# frontplatine_v0_2.net
KiCad netlist of a schematic drawn in EAGLE
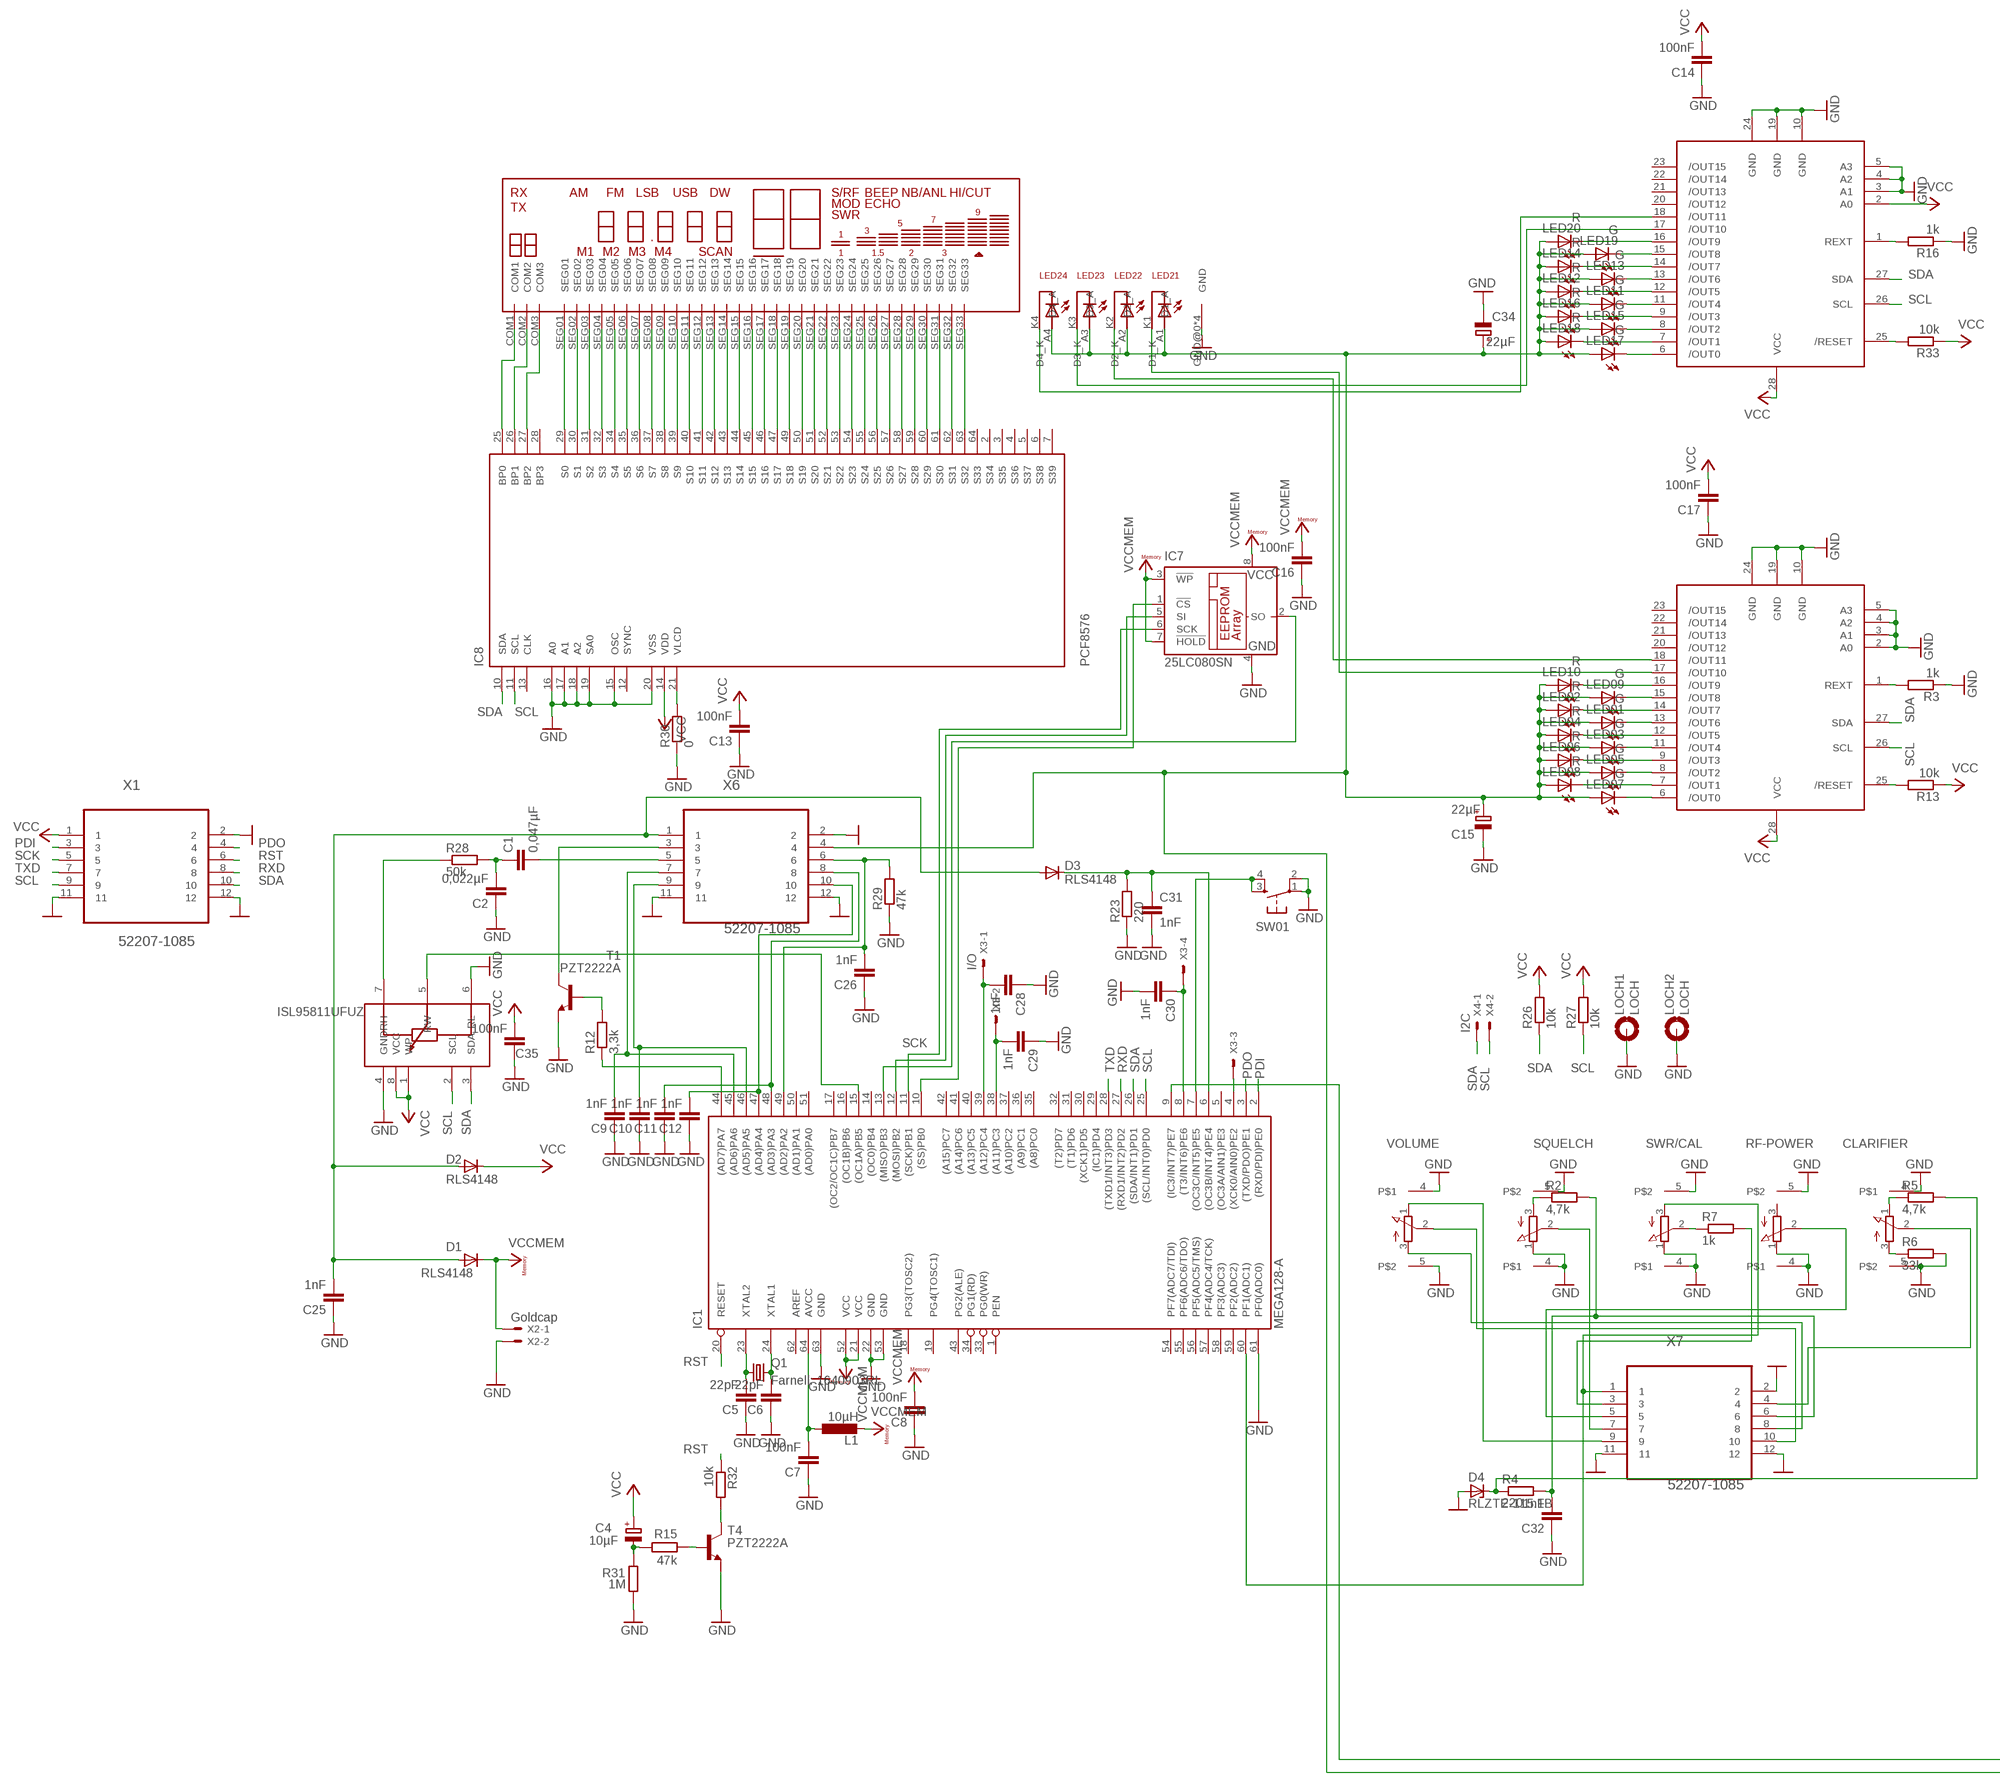
[diagram p0: schematic, sheet 1, part 1 of 2]
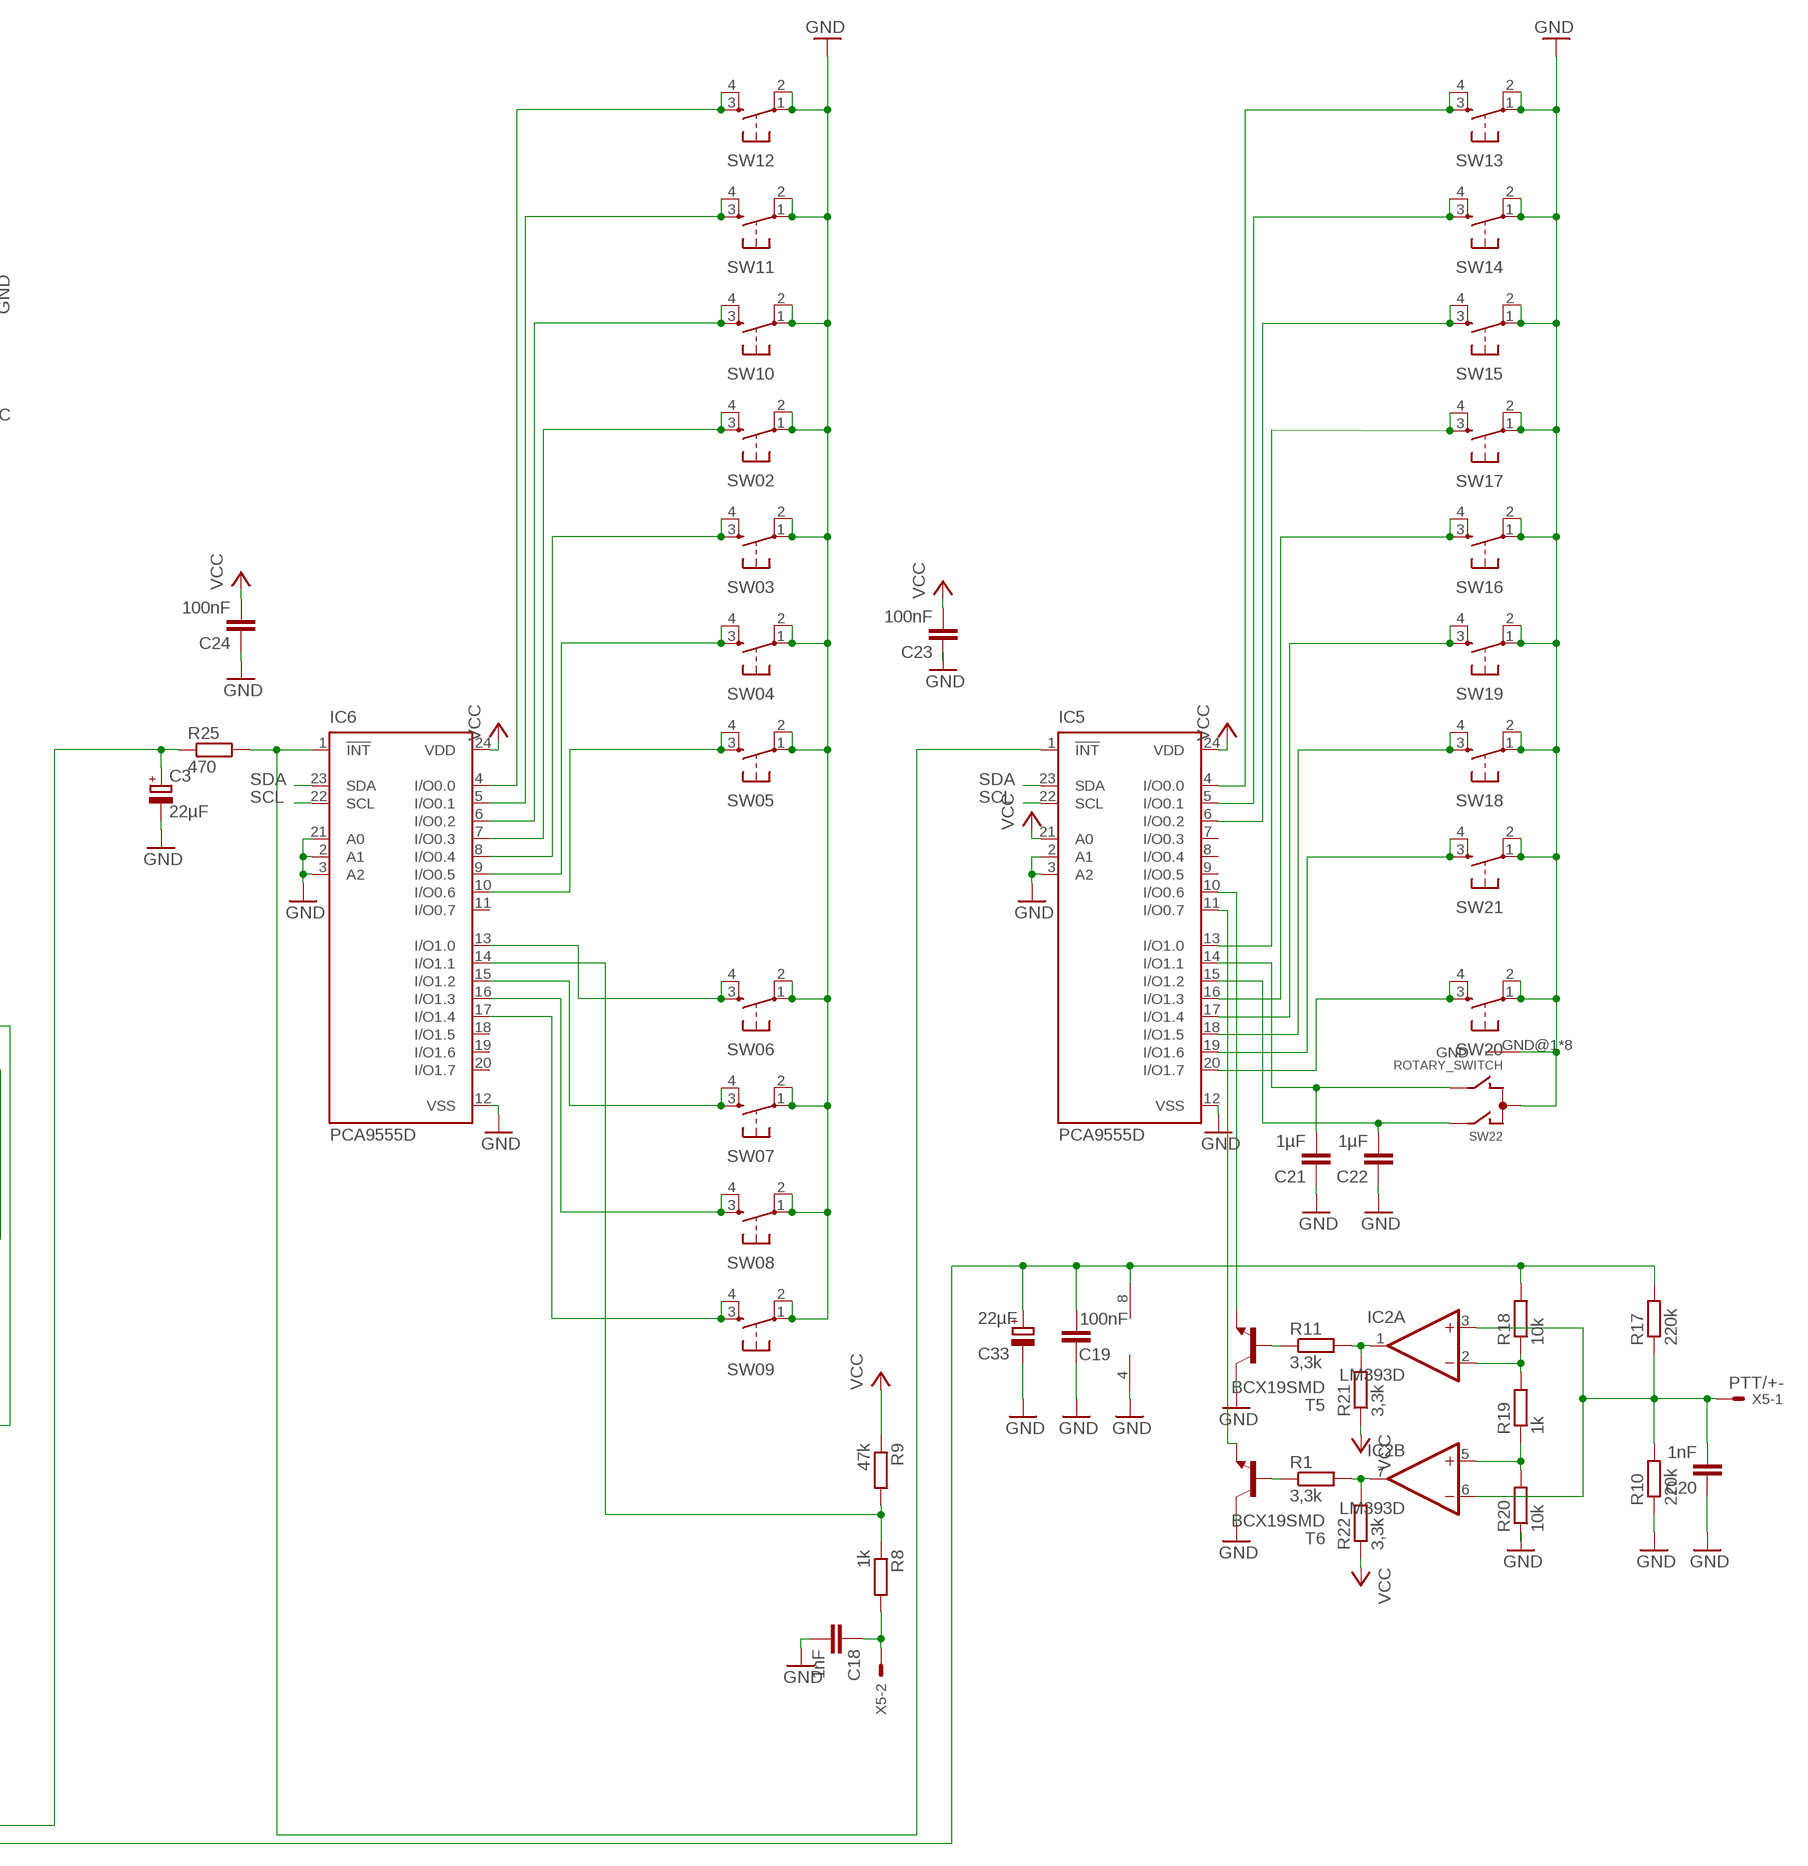
[diagram p1: schematic, sheet 1, part 2 of 2]

(export (version "E")
  (design (tool "Eeschema 10.0.6"))
  (components
    (comp (ref "C1")
      (value "0,047µF")
      (footprint "eagle-import:C1206")
      (libsource (lib "eagle-import") (part "C-EUC1206"))
    )
    (comp (ref "C2")
      (value "0,022µF")
      (footprint "eagle-import:C1206")
      (libsource (lib "eagle-import") (part "resistor_C-EUC1206"))
    )
    (comp (ref "C3")
      (value "22µF")
      (footprint "eagle-import:CT3216")
      (libsource (lib "eagle-import") (part "CPOL-EUCT3216"))
    )
    (comp (ref "C4")
      (value "10µF")
      (footprint "eagle-import:CT3216")
      (libsource (lib "eagle-import") (part "CPOL-EUCT3216"))
    )
    (comp (ref "C5")
      (value "22pF")
      (footprint "eagle-import:C1206")
      (libsource (lib "eagle-import") (part "resistor_C-EUC1206"))
    )
    (comp (ref "C6")
      (value "22pF")
      (footprint "eagle-import:C1206")
      (libsource (lib "eagle-import") (part "resistor_C-EUC1206"))
    )
    (comp (ref "C7")
      (value "100nF")
      (footprint "eagle-import:C1206")
      (libsource (lib "eagle-import") (part "resistor_C-EUC1206"))
    )
    (comp (ref "C8")
      (value "100nF")
      (footprint "eagle-import:C1206")
      (libsource (lib "eagle-import") (part "resistor_C-EUC1206"))
    )
    (comp (ref "C9")
      (value "1nF")
      (footprint "eagle-import:C1206")
      (libsource (lib "eagle-import") (part "resistor_C-EUC1206"))
    )
    (comp (ref "C10")
      (value "1nF")
      (footprint "eagle-import:C1206")
      (libsource (lib "eagle-import") (part "resistor_C-EUC1206"))
    )
    (comp (ref "C11")
      (value "1nF")
      (footprint "eagle-import:C1206")
      (libsource (lib "eagle-import") (part "resistor_C-EUC1206"))
    )
    (comp (ref "C12")
      (value "1nF")
      (footprint "eagle-import:C1206")
      (libsource (lib "eagle-import") (part "resistor_C-EUC1206"))
    )
    (comp (ref "C13")
      (value "100nF")
      (footprint "eagle-import:C1206")
      (libsource (lib "eagle-import") (part "resistor_C-EUC1206"))
    )
    (comp (ref "C14")
      (value "100nF")
      (footprint "eagle-import:C1206")
      (libsource (lib "eagle-import") (part "resistor_C-EUC1206"))
    )
    (comp (ref "C15")
      (value "22µF")
      (footprint "eagle-import:CT3216")
      (libsource (lib "eagle-import") (part "CPOL-EUCT3216"))
    )
    (comp (ref "C16")
      (value "100nF")
      (footprint "eagle-import:C1206")
      (libsource (lib "eagle-import") (part "resistor_C-EUC1206"))
    )
    (comp (ref "C17")
      (value "100nF")
      (footprint "eagle-import:C1206")
      (libsource (lib "eagle-import") (part "resistor_C-EUC1206"))
    )
    (comp (ref "C18")
      (value "1nF")
      (footprint "eagle-import:C1206")
      (libsource (lib "eagle-import") (part "resistor_C-EUC1206"))
    )
    (comp (ref "C19")
      (value "100nF")
      (footprint "eagle-import:C1206")
      (libsource (lib "eagle-import") (part "resistor_C-EUC1206"))
    )
    (comp (ref "C20")
      (value "1nF")
      (footprint "eagle-import:C1206")
      (libsource (lib "eagle-import") (part "resistor_C-EUC1206"))
    )
    (comp (ref "C21")
      (value "1µF")
      (footprint "eagle-import:C1206")
      (libsource (lib "eagle-import") (part "resistor_C-EUC1206"))
    )
    (comp (ref "C22")
      (value "1µF")
      (footprint "eagle-import:C1206")
      (libsource (lib "eagle-import") (part "resistor_C-EUC1206"))
    )
    (comp (ref "C23")
      (value "100nF")
      (footprint "eagle-import:C1206")
      (libsource (lib "eagle-import") (part "resistor_C-EUC1206"))
    )
    (comp (ref "C24")
      (value "100nF")
      (footprint "eagle-import:C1206")
      (libsource (lib "eagle-import") (part "resistor_C-EUC1206"))
    )
    (comp (ref "C25")
      (value "1nF")
      (footprint "eagle-import:C1206")
      (libsource (lib "eagle-import") (part "resistor_C-EUC1206"))
    )
    (comp (ref "C26")
      (value "1nF")
      (footprint "eagle-import:C1206")
      (libsource (lib "eagle-import") (part "resistor_C-EUC1206"))
    )
    (comp (ref "C28")
      (value "1nF")
      (footprint "eagle-import:C1206")
      (libsource (lib "eagle-import") (part "resistor_C-EUC1206"))
    )
    (comp (ref "C29")
      (value "1nF")
      (footprint "eagle-import:C1206")
      (libsource (lib "eagle-import") (part "resistor_C-EUC1206"))
    )
    (comp (ref "C30")
      (value "1nF")
      (footprint "eagle-import:C1206")
      (libsource (lib "eagle-import") (part "resistor_C-EUC1206"))
    )
    (comp (ref "C31")
      (value "1nF")
      (footprint "eagle-import:C1206")
      (libsource (lib "eagle-import") (part "resistor_C-EUC1206"))
    )
    (comp (ref "C32")
      (value "1nF")
      (footprint "eagle-import:C1206")
      (libsource (lib "eagle-import") (part "resistor_C-EUC1206"))
    )
    (comp (ref "C33")
      (value "22µF")
      (footprint "eagle-import:CT3216")
      (libsource (lib "eagle-import") (part "CPOL-EUCT3216"))
    )
    (comp (ref "C34")
      (value "22µF")
      (footprint "eagle-import:CT3216")
      (libsource (lib "eagle-import") (part "CPOL-EUCT3216"))
    )
    (comp (ref "C35")
      (value "100nF")
      (footprint "eagle-import:C1206")
      (libsource (lib "eagle-import") (part "resistor_C-EUC1206"))
    )
    (comp (ref "CLARIFIER")
      (value "POTI")
      (footprint "eagle-import:POTI")
      (libsource (lib "eagle-import") (part "POTI"))
    )
    (comp (ref "D1")
      (value "RLS4148")
      (footprint "eagle-import:SOD80C")
      (libsource (lib "eagle-import") (part "DIODE-SOD80C"))
    )
    (comp (ref "D2")
      (value "RLS4148")
      (footprint "eagle-import:SOD80C")
      (libsource (lib "eagle-import") (part "DIODE-SOD80C"))
    )
    (comp (ref "D3")
      (value "RLS4148")
      (footprint "eagle-import:SOD80C")
      (libsource (lib "eagle-import") (part "DIODE-SOD80C"))
    )
    (comp (ref "D4")
      (value "RLZTE-115.1B")
      (footprint "eagle-import:SOD80C")
      (libsource (lib "eagle-import") (part "ZENER-DIODESOD80C"))
    )
    (comp (ref "DISPLAY1")
      (value "DISPLAY")
      (footprint "eagle-import:DISPLAY")
      (libsource (lib "eagle-import") (part "DISPLAY"))
    )
    (comp (ref "IC1")
      (value "MEGA128-A")
      (footprint "eagle-import:TQFP64")
      (fields (field (name "MPN") "ATMEGA128-16AU"))
      (libsource (lib "eagle-import") (part "MEGA128-A"))
    )
    (comp (ref "IC2")
      (value "LM393D")
      (footprint "eagle-import:SO08")
      (libsource (lib "eagle-import") (part "LM393D"))
    )
    (comp (ref "IC3")
      (value "TLC59116")
      (footprint "eagle-import:TSSOP28")
      (libsource (lib "eagle-import") (part "TLC59116"))
    )
    (comp (ref "IC4")
      (value "TLC59116")
      (footprint "eagle-import:TSSOP28")
      (libsource (lib "eagle-import") (part "TLC59116"))
    )
    (comp (ref "IC5")
      (value "PCA9555D")
      (footprint "eagle-import:SO24")
      (fields (field (name "MPN") "PCA9555DW"))
      (libsource (lib "eagle-import") (part "PCA9555D"))
    )
    (comp (ref "IC6")
      (value "PCA9555D")
      (footprint "eagle-import:SO24")
      (fields (field (name "MPN") "PCA9555DW"))
      (libsource (lib "eagle-import") (part "PCA9555D"))
    )
    (comp (ref "IC7")
      (value "25LC080SN")
      (footprint "eagle-import:SO-08")
      (fields
        (field (name "MF") "MICROCHIP")
        (field (name "MPN") "25LC080/SN")
        (field (name "MPN_1") "25LC080/SN")
        (field (name "OC_FARNELL") "1137302")
        (field (name "OC_NEWARK") "96K4092")
      )
      (libsource (lib "eagle-import") (part "25SNLC080"))
    )
    (comp (ref "IC8")
      (value "PCF8576")
      (footprint "eagle-import:LQFP-ST-64-2")
      (libsource (lib "eagle-import") (part "PCF8576"))
    )
    (comp (ref "IC9")
      (value "ISL95811UFUZ")
      (footprint "eagle-import:MSOP8")
      (libsource (lib "eagle-import") (part "ISL95811UFUZ"))
    )
    (comp (ref "L1")
      (value "10µH")
      (footprint "eagle-import:L1812")
      (libsource (lib "eagle-import") (part "L-EUL1812"))
    )
    (comp (ref "LED01")
      (value "G")
      (footprint "eagle-import:CHIPLED_1206")
      (libsource (lib "eagle-import") (part "LEDCHIPLED_1206"))
    )
    (comp (ref "LED02")
      (value "R")
      (footprint "eagle-import:CHIPLED_1206")
      (libsource (lib "eagle-import") (part "LEDCHIPLED_1206"))
    )
    (comp (ref "LED03")
      (value "G")
      (footprint "eagle-import:CHIPLED_1206")
      (libsource (lib "eagle-import") (part "LEDCHIPLED_1206"))
    )
    (comp (ref "LED04")
      (value "R")
      (footprint "eagle-import:CHIPLED_1206")
      (libsource (lib "eagle-import") (part "LEDCHIPLED_1206"))
    )
    (comp (ref "LED05")
      (value "G")
      (footprint "eagle-import:CHIPLED_1206")
      (libsource (lib "eagle-import") (part "LEDCHIPLED_1206"))
    )
    (comp (ref "LED06")
      (value "R")
      (footprint "eagle-import:CHIPLED_1206")
      (libsource (lib "eagle-import") (part "LEDCHIPLED_1206"))
    )
    (comp (ref "LED07")
      (value "G")
      (footprint "eagle-import:CHIPLED_1206")
      (libsource (lib "eagle-import") (part "LEDCHIPLED_1206"))
    )
    (comp (ref "LED08")
      (value "R")
      (footprint "eagle-import:CHIPLED_1206")
      (libsource (lib "eagle-import") (part "LEDCHIPLED_1206"))
    )
    (comp (ref "LED09")
      (value "G")
      (footprint "eagle-import:CHIPLED_1206")
      (libsource (lib "eagle-import") (part "LEDCHIPLED_1206"))
    )
    (comp (ref "LED10")
      (value "R")
      (footprint "eagle-import:CHIPLED_1206")
      (libsource (lib "eagle-import") (part "LEDCHIPLED_1206"))
    )
    (comp (ref "LED11")
      (value "G")
      (footprint "eagle-import:CHIPLED_1206")
      (libsource (lib "eagle-import") (part "LEDCHIPLED_1206"))
    )
    (comp (ref "LED12")
      (value "R")
      (footprint "eagle-import:CHIPLED_1206")
      (libsource (lib "eagle-import") (part "LEDCHIPLED_1206"))
    )
    (comp (ref "LED13")
      (value "G")
      (footprint "eagle-import:CHIPLED_1206")
      (libsource (lib "eagle-import") (part "LEDCHIPLED_1206"))
    )
    (comp (ref "LED14")
      (value "R")
      (footprint "eagle-import:CHIPLED_1206")
      (libsource (lib "eagle-import") (part "LEDCHIPLED_1206"))
    )
    (comp (ref "LED15")
      (value "G")
      (footprint "eagle-import:CHIPLED_1206")
      (libsource (lib "eagle-import") (part "LEDCHIPLED_1206"))
    )
    (comp (ref "LED16")
      (value "R")
      (footprint "eagle-import:CHIPLED_1206")
      (libsource (lib "eagle-import") (part "LEDCHIPLED_1206"))
    )
    (comp (ref "LED17")
      (value "G")
      (footprint "eagle-import:CHIPLED_1206")
      (libsource (lib "eagle-import") (part "LEDCHIPLED_1206"))
    )
    (comp (ref "LED18")
      (value "R")
      (footprint "eagle-import:CHIPLED_1206")
      (libsource (lib "eagle-import") (part "LEDCHIPLED_1206"))
    )
    (comp (ref "LED19")
      (value "G")
      (footprint "eagle-import:CHIPLED_1206")
      (libsource (lib "eagle-import") (part "LEDCHIPLED_1206"))
    )
    (comp (ref "LED20")
      (value "R")
      (footprint "eagle-import:CHIPLED_1206")
      (libsource (lib "eagle-import") (part "LEDCHIPLED_1206"))
    )
    (comp (ref "LOCH1")
      (value "LOCH")
      (footprint "eagle-import:LOCH")
      (libsource (lib "eagle-import") (part "LOCH"))
    )
    (comp (ref "LOCH2")
      (value "LOCH")
      (footprint "eagle-import:LOCH")
      (libsource (lib "eagle-import") (part "LOCH"))
    )
    (comp (ref "Q1")
      (value "Farnell: 1640903RL")
      (footprint "eagle-import:HC49UP")
      (libsource (lib "eagle-import") (part "CRYSTALHC49UP"))
    )
    (comp (ref "R1")
      (value "3,3k")
      (footprint "eagle-import:R1206")
      (libsource (lib "eagle-import") (part "resistor_R-EU_R1206"))
    )
    (comp (ref "R2")
      (value "4,7k")
      (footprint "eagle-import:R1206")
      (libsource (lib "eagle-import") (part "resistor_R-EU_R1206"))
    )
    (comp (ref "R3")
      (value "1k")
      (footprint "eagle-import:R1206")
      (libsource (lib "eagle-import") (part "R-EU_R1206"))
    )
    (comp (ref "R4")
      (value "220")
      (footprint "eagle-import:R1206")
      (libsource (lib "eagle-import") (part "resistor_R-EU_R1206"))
    )
    (comp (ref "R5")
      (value "4,7k")
      (footprint "eagle-import:R1206")
      (libsource (lib "eagle-import") (part "resistor_R-EU_R1206"))
    )
    (comp (ref "R6")
      (value "33k")
      (footprint "eagle-import:R1206")
      (libsource (lib "eagle-import") (part "resistor_R-EU_R1206"))
    )
    (comp (ref "R7")
      (value "1k")
      (footprint "eagle-import:R1206")
      (libsource (lib "eagle-import") (part "resistor_R-EU_R1206"))
    )
    (comp (ref "R8")
      (value "1k")
      (footprint "eagle-import:R1206")
      (libsource (lib "eagle-import") (part "resistor_R-EU_R1206"))
    )
    (comp (ref "R9")
      (value "47k")
      (footprint "eagle-import:R1206")
      (libsource (lib "eagle-import") (part "resistor_R-EU_R1206"))
    )
    (comp (ref "R10")
      (value "220k")
      (footprint "eagle-import:R1206")
      (libsource (lib "eagle-import") (part "resistor_R-EU_R1206"))
    )
    (comp (ref "R11")
      (value "3,3k")
      (footprint "eagle-import:R1206")
      (libsource (lib "eagle-import") (part "resistor_R-EU_R1206"))
    )
    (comp (ref "R12")
      (value "3,3k")
      (footprint "eagle-import:R1206")
      (libsource (lib "eagle-import") (part "resistor_R-EU_R1206"))
    )
    (comp (ref "R13")
      (value "10k")
      (footprint "eagle-import:R1206")
      (libsource (lib "eagle-import") (part "resistor_R-EU_R1206"))
    )
    (comp (ref "R15")
      (value "47k")
      (footprint "eagle-import:R1206")
      (libsource (lib "eagle-import") (part "resistor_R-EU_R1206"))
    )
    (comp (ref "R16")
      (value "1k")
      (footprint "eagle-import:R1206")
      (libsource (lib "eagle-import") (part "R-EU_R1206"))
    )
    (comp (ref "R17")
      (value "220k")
      (footprint "eagle-import:R1206")
      (libsource (lib "eagle-import") (part "resistor_R-EU_R1206"))
    )
    (comp (ref "R18")
      (value "10k")
      (footprint "eagle-import:R1206")
      (libsource (lib "eagle-import") (part "resistor_R-EU_R1206"))
    )
    (comp (ref "R19")
      (value "1k")
      (footprint "eagle-import:R1206")
      (libsource (lib "eagle-import") (part "resistor_R-EU_R1206"))
    )
    (comp (ref "R20")
      (value "10k")
      (footprint "eagle-import:R1206")
      (libsource (lib "eagle-import") (part "resistor_R-EU_R1206"))
    )
    (comp (ref "R21")
      (value "3,3k")
      (footprint "eagle-import:R1206")
      (libsource (lib "eagle-import") (part "resistor_R-EU_R1206"))
    )
    (comp (ref "R22")
      (value "3,3k")
      (footprint "eagle-import:R1206")
      (libsource (lib "eagle-import") (part "resistor_R-EU_R1206"))
    )
    (comp (ref "R23")
      (value "220")
      (footprint "eagle-import:R1206")
      (libsource (lib "eagle-import") (part "resistor_R-EU_R1206"))
    )
    (comp (ref "R25")
      (value "470")
      (footprint "eagle-import:R1206")
      (libsource (lib "eagle-import") (part "resistor_R-EU_R1206"))
    )
    (comp (ref "R26")
      (value "10k")
      (footprint "eagle-import:R1206")
      (libsource (lib "eagle-import") (part "resistor_R-EU_R1206"))
    )
    (comp (ref "R27")
      (value "10k")
      (footprint "eagle-import:R1206")
      (libsource (lib "eagle-import") (part "resistor_R-EU_R1206"))
    )
    (comp (ref "R28")
      (value "50k")
      (footprint "eagle-import:R1206")
      (libsource (lib "eagle-import") (part "resistor_R-EU_R1206"))
    )
    (comp (ref "R29")
      (value "47k")
      (footprint "eagle-import:R1206")
      (libsource (lib "eagle-import") (part "resistor_R-EU_R1206"))
    )
    (comp (ref "R30")
      (value "0")
      (footprint "eagle-import:R1206")
      (libsource (lib "eagle-import") (part "resistor_R-EU_R1206"))
    )
    (comp (ref "R31")
      (value "1M")
      (footprint "eagle-import:R1206")
      (libsource (lib "eagle-import") (part "resistor_R-EU_R1206"))
    )
    (comp (ref "R32")
      (value "10k")
      (footprint "eagle-import:R1206")
      (libsource (lib "eagle-import") (part "resistor_R-EU_R1206"))
    )
    (comp (ref "R33")
      (value "10k")
      (footprint "eagle-import:R1206")
      (libsource (lib "eagle-import") (part "resistor_R-EU_R1206"))
    )
    (comp (ref "RF-POWER")
      (value "POTI")
      (footprint "eagle-import:POTI")
      (libsource (lib "eagle-import") (part "POTI"))
    )
    (comp (ref "SQUELCH")
      (value "POTI")
      (footprint "eagle-import:POTI")
      (libsource (lib "eagle-import") (part "POTI"))
    )
    (comp (ref "SW01")
      (value "TASTER")
      (footprint "eagle-import:TASTER")
      (libsource (lib "eagle-import") (part "TASTER"))
    )
    (comp (ref "SW02")
      (value "TASTER")
      (footprint "eagle-import:TASTER")
      (libsource (lib "eagle-import") (part "TASTER"))
    )
    (comp (ref "SW03")
      (value "TASTER")
      (footprint "eagle-import:TASTER")
      (libsource (lib "eagle-import") (part "TASTER"))
    )
    (comp (ref "SW04")
      (value "TASTER")
      (footprint "eagle-import:TASTER")
      (libsource (lib "eagle-import") (part "TASTER"))
    )
    (comp (ref "SW05")
      (value "TASTER")
      (footprint "eagle-import:TASTER")
      (libsource (lib "eagle-import") (part "TASTER"))
    )
    (comp (ref "SW06")
      (value "TASTER")
      (footprint "eagle-import:TASTER")
      (libsource (lib "eagle-import") (part "TASTER"))
    )
    (comp (ref "SW07")
      (value "TASTER")
      (footprint "eagle-import:TASTER")
      (libsource (lib "eagle-import") (part "TASTER"))
    )
    (comp (ref "SW08")
      (value "TASTER")
      (footprint "eagle-import:TASTER")
      (libsource (lib "eagle-import") (part "TASTER"))
    )
    (comp (ref "SW09")
      (value "TASTER")
      (footprint "eagle-import:TASTER")
      (libsource (lib "eagle-import") (part "TASTER"))
    )
    (comp (ref "SW10")
      (value "TASTER")
      (footprint "eagle-import:TASTER")
      (libsource (lib "eagle-import") (part "TASTER"))
    )
    (comp (ref "SW11")
      (value "TASTER")
      (footprint "eagle-import:TASTER")
      (libsource (lib "eagle-import") (part "TASTER"))
    )
    (comp (ref "SW12")
      (value "TASTER")
      (footprint "eagle-import:TASTER")
      (libsource (lib "eagle-import") (part "TASTER"))
    )
    (comp (ref "SW13")
      (value "TASTER")
      (footprint "eagle-import:TASTER")
      (libsource (lib "eagle-import") (part "TASTER"))
    )
    (comp (ref "SW14")
      (value "TASTER")
      (footprint "eagle-import:TASTER")
      (libsource (lib "eagle-import") (part "TASTER"))
    )
    (comp (ref "SW15")
      (value "TASTER")
      (footprint "eagle-import:TASTER")
      (libsource (lib "eagle-import") (part "TASTER"))
    )
    (comp (ref "SW16")
      (value "TASTER")
      (footprint "eagle-import:TASTER")
      (libsource (lib "eagle-import") (part "TASTER"))
    )
    (comp (ref "SW17")
      (value "TASTER")
      (footprint "eagle-import:TASTER")
      (libsource (lib "eagle-import") (part "TASTER"))
    )
    (comp (ref "SW18")
      (value "TASTER")
      (footprint "eagle-import:TASTER")
      (libsource (lib "eagle-import") (part "TASTER"))
    )
    (comp (ref "SW19")
      (value "TASTER")
      (footprint "eagle-import:TASTER")
      (libsource (lib "eagle-import") (part "TASTER"))
    )
    (comp (ref "SW20")
      (value "TASTER")
      (footprint "eagle-import:TASTER")
      (libsource (lib "eagle-import") (part "TASTER"))
    )
    (comp (ref "SW21")
      (value "TASTER")
      (footprint "eagle-import:TASTER")
      (libsource (lib "eagle-import") (part "TASTER"))
    )
    (comp (ref "SW22")
      (value "ROTARY_SWITCH")
      (footprint "eagle-import:ROTARY_SWITCH")
      (libsource (lib "eagle-import") (part "ROTARY_SWITCH"))
    )
    (comp (ref "SWR/CAL")
      (value "POTI")
      (footprint "eagle-import:POTI")
      (libsource (lib "eagle-import") (part "POTI"))
    )
    (comp (ref "T1")
      (value "PZT2222A")
      (footprint "eagle-import:SOT223")
      (libsource (lib "eagle-import") (part "-NPN-SOT223PZT2222A"))
    )
    (comp (ref "T4")
      (value "PZT2222A")
      (footprint "eagle-import:SOT223")
      (libsource (lib "eagle-import") (part "-NPN-SOT223PZT2222A"))
    )
    (comp (ref "T5")
      (value "BCX19SMD")
      (footprint "eagle-import:SOT23-BEC")
      (libsource (lib "eagle-import") (part "BCX19SMD"))
    )
    (comp (ref "T6")
      (value "BCX19SMD")
      (footprint "eagle-import:SOT23-BEC")
      (libsource (lib "eagle-import") (part "BCX19SMD"))
    )
    (comp (ref "VOLUME")
      (value "POTI")
      (footprint "eagle-import:POTI")
      (libsource (lib "eagle-import") (part "POTI"))
    )
    (comp (ref "X1")
      (value "52207-1085")
      (footprint "eagle-import:MOLEX_52207-1085")
      (libsource (lib "eagle-import") (part "52207-1085"))
    )
    (comp (ref "X2")
      (value "Goldcap")
      (footprint "eagle-import:53047-02")
      (fields (field (name "MF") "MOLEX") (field (name "MPN") "53047-0210"))
      (libsource (lib "eagle-import") (part "53?-02047"))
    )
    (comp (ref "X3")
      (value "I/O")
      (footprint "eagle-import:53047-04")
      (fields (field (name "MF") "WALDOM/MOLEX") (field (name "MPN") "53047-0410"))
      (libsource (lib "eagle-import") (part "53?-04047"))
    )
    (comp (ref "X4")
      (value "I2C")
      (footprint "eagle-import:53047-02")
      (fields
        (field (name "MF") "MOLEX")
        (field (name "MPN") "53047-0210")
        (field (name "MF_1") "MOLEX")
        (field (name "MPN_1") "53047-0210")
        (field (name "OC_FARNELL") "9733051")
        (field (name "OC_NEWARK") "57H4701")
      )
      (libsource (lib "eagle-import") (part "53?-02047"))
    )
    (comp (ref "X5")
      (value "PTT/+-")
      (footprint "eagle-import:53047-02")
      (fields
        (field (name "MF") "MOLEX")
        (field (name "MPN") "53047-0210")
        (field (name "MF_1") "MOLEX")
        (field (name "MPN_1") "53047-0210")
        (field (name "OC_FARNELL") "9733051")
        (field (name "OC_NEWARK") "57H4701")
      )
      (libsource (lib "eagle-import") (part "53?-02047"))
    )
    (comp (ref "X6")
      (value "52207-1085")
      (footprint "eagle-import:MOLEX_52207-1085")
      (fields
        (field (name "MPN") "52207-1085")
        (field (name "OC_FARNELL") "1079938")
        (field (name "OC_NEWARK") "58J9503")
        (field (name "PACKAGE") "SOCKET FPC, SMT, 1MM, 10 WAY")
      )
      (libsource (lib "eagle-import") (part "52207-1085"))
    )
    (comp (ref "X7")
      (value "52207-1085")
      (footprint "eagle-import:MOLEX_52207-1085")
      (fields
        (field (name "MPN") "52207-1085")
        (field (name "OC_FARNELL") "1079938")
        (field (name "OC_NEWARK") "58J9503")
        (field (name "PACKAGE") "SOCKET FPC, SMT, 1MM, 10 WAY")
      )
      (libsource (lib "eagle-import") (part "52207-1085"))
    )
  )
  (nets
    (net (code "1") (name "/PDI") (class "Default")
      (node (ref "IC1") (pin "2") (pinfunction "(RXD/PDI)PE0_2") (pintype "bidirectional"))
      (node (ref "X1") (pin "3") (pinfunction "3_3") (pintype "passive"))
    )
    (net (code "2") (name "/PDO") (class "Default")
      (node (ref "IC1") (pin "3") (pinfunction "(TXD/PDO)PE1_3") (pintype "bidirectional"))
      (node (ref "X1") (pin "4") (pinfunction "4_4") (pintype "passive"))
    )
    (net (code "3") (name "/RST") (class "Default")
      (node (ref "IC1") (pin "20") (pinfunction "RESET_20") (pintype "input"))
      (node (ref "R32") (pin "1") (pinfunction "1_1") (pintype "passive"))
      (node (ref "X1") (pin "6") (pinfunction "6_6") (pintype "passive"))
    )
    (net (code "4") (name "/RXD") (class "Default")
      (node (ref "IC1") (pin "27") (pinfunction "(RXD1/INT2)PD2_27") (pintype "bidirectional"))
      (node (ref "X1") (pin "8") (pinfunction "8_8") (pintype "passive"))
    )
    (net (code "5") (name "/SCK") (class "Default")
      (node (ref "IC1") (pin "11") (pinfunction "(SCK)PB1_11") (pintype "bidirectional"))
      (node (ref "IC7") (pin "6") (pinfunction "SCK_6") (pintype "input"))
      (node (ref "X1") (pin "5") (pinfunction "5_5") (pintype "passive"))
    )
    (net (code "6") (name "/SCL") (class "Default")
      (node (ref "IC1") (pin "25") (pinfunction "(SCL/INT0)PD0_25") (pintype "bidirectional"))
      (node (ref "IC3") (pin "26") (pinfunction "SCL_26") (pintype "bidirectional"))
      (node (ref "IC4") (pin "26") (pinfunction "SCL_26") (pintype "bidirectional"))
      (node (ref "IC5") (pin "22") (pinfunction "SCL_22") (pintype "input"))
      (node (ref "IC6") (pin "22") (pinfunction "SCL_22") (pintype "input"))
      (node (ref "IC8") (pin "11") (pinfunction "SCL_11") (pintype "input"))
      (node (ref "IC9") (pin "2") (pinfunction "SCL_2") (pintype "bidirectional"))
      (node (ref "R27") (pin "1") (pinfunction "1_1") (pintype "passive"))
      (node (ref "X1") (pin "9") (pinfunction "9_9") (pintype "passive"))
      (node (ref "X4") (pin "2") (pinfunction "S_2") (pintype "passive"))
    )
    (net (code "7") (name "/SDA") (class "Default")
      (node (ref "IC1") (pin "26") (pinfunction "(SDA/INT1)PD1_26") (pintype "bidirectional"))
      (node (ref "IC3") (pin "27") (pinfunction "SDA_27") (pintype "bidirectional"))
      (node (ref "IC4") (pin "27") (pinfunction "SDA_27") (pintype "bidirectional"))
      (node (ref "IC5") (pin "23") (pinfunction "SDA_23") (pintype "bidirectional"))
      (node (ref "IC6") (pin "23") (pinfunction "SDA_23") (pintype "bidirectional"))
      (node (ref "IC8") (pin "10") (pinfunction "SDA_10") (pintype "bidirectional"))
      (node (ref "IC9") (pin "3") (pinfunction "SDA_3") (pintype "input"))
      (node (ref "R26") (pin "1") (pinfunction "1_1") (pintype "passive"))
      (node (ref "X1") (pin "10") (pinfunction "10_10") (pintype "passive"))
      (node (ref "X4") (pin "1") (pinfunction "S_1") (pintype "passive"))
    )
    (net (code "8") (name "/TXD") (class "Default")
      (node (ref "IC1") (pin "28") (pinfunction "(TXD1/INT3)PD3_28") (pintype "bidirectional"))
      (node (ref "X1") (pin "7") (pinfunction "7_7") (pintype "passive"))
    )
    (net (code "9") (name "GND") (class "Default")
      (node (ref "C10") (pin "1") (pinfunction "1_1") (pintype "passive"))
      (node (ref "C11") (pin "1") (pinfunction "1_1") (pintype "passive"))
      (node (ref "C12") (pin "1") (pinfunction "1_1") (pintype "passive"))
      (node (ref "C13") (pin "1") (pinfunction "1_1") (pintype "passive"))
      (node (ref "C14") (pin "1") (pinfunction "1_1") (pintype "passive"))
      (node (ref "C15") (pin "-") (pinfunction "-_-") (pintype "passive"))
      (node (ref "C16") (pin "1") (pinfunction "1_1") (pintype "passive"))
      (node (ref "C17") (pin "1") (pinfunction "1_1") (pintype "passive"))
      (node (ref "C18") (pin "2") (pinfunction "2_2") (pintype "passive"))
      (node (ref "C19") (pin "1") (pinfunction "1_1") (pintype "passive"))
      (node (ref "C2") (pin "1") (pinfunction "1_1") (pintype "passive"))
      (node (ref "C20") (pin "1") (pinfunction "1_1") (pintype "passive"))
      (node (ref "C21") (pin "1") (pinfunction "1_1") (pintype "passive"))
      (node (ref "C22") (pin "1") (pinfunction "1_1") (pintype "passive"))
      (node (ref "C23") (pin "1") (pinfunction "1_1") (pintype "passive"))
      (node (ref "C24") (pin "1") (pinfunction "1_1") (pintype "passive"))
      (node (ref "C25") (pin "1") (pinfunction "1_1") (pintype "passive"))
      (node (ref "C26") (pin "1") (pinfunction "1_1") (pintype "passive"))
      (node (ref "C28") (pin "1") (pinfunction "1_1") (pintype "passive"))
      (node (ref "C29") (pin "1") (pinfunction "1_1") (pintype "passive"))
      (node (ref "C3") (pin "-") (pinfunction "-_-") (pintype "passive"))
      (node (ref "C30") (pin "2") (pinfunction "2_2") (pintype "passive"))
      (node (ref "C31") (pin "2") (pinfunction "2_2") (pintype "passive"))
      (node (ref "C32") (pin "1") (pinfunction "1_1") (pintype "passive"))
      (node (ref "C33") (pin "-") (pinfunction "-_-") (pintype "passive"))
      (node (ref "C34") (pin "-") (pinfunction "-_-") (pintype "passive"))
      (node (ref "C35") (pin "1") (pinfunction "1_1") (pintype "passive"))
      (node (ref "C5") (pin "1") (pinfunction "1_1") (pintype "passive"))
      (node (ref "C6") (pin "1") (pinfunction "1_1") (pintype "passive"))
      (node (ref "C7") (pin "1") (pinfunction "1_1") (pintype "passive"))
      (node (ref "C8") (pin "1") (pinfunction "1_1") (pintype "passive"))
      (node (ref "C9") (pin "1") (pinfunction "1_1") (pintype "passive"))
      (node (ref "CLARIFIER") (pin "4") (pinfunction "P$1_4") (pintype "power_in"))
      (node (ref "CLARIFIER") (pin "5") (pinfunction "P$2_5") (pintype "power_in"))
      (node (ref "D4") (pin "A") (pinfunction "A_A") (pintype "passive"))
      (node (ref "DISPLAY1") (pin "GND@0") (pinfunction "GND_GND@0") (pintype "power_in"))
      (node (ref "DISPLAY1") (pin "GND@3") (pinfunction "GND_GND@3") (pintype "power_in"))
      (node (ref "DISPLAY1") (pin "GND@6") (pinfunction "GND_GND@6") (pintype "power_in"))
      (node (ref "DISPLAY1") (pin "GND@7") (pinfunction "GND_GND@7") (pintype "power_in"))
      (node (ref "IC1") (pin "22") (pinfunction "GND_22") (pintype "power_in"))
      (node (ref "IC1") (pin "53") (pinfunction "GND_53") (pintype "power_in"))
      (node (ref "IC1") (pin "61") (pinfunction "PF0(ADC0)_61") (pintype "input"))
      (node (ref "IC1") (pin "63") (pinfunction "GND_63") (pintype "power_in"))
      (node (ref "IC2") (pin "4") (pinfunction "V-_4") (pintype "power_in"))
      (node (ref "IC3") (pin "10") (pinfunction "GND_10") (pintype "bidirectional"))
      (node (ref "IC3") (pin "19") (pinfunction "GND_19") (pintype "bidirectional"))
      (node (ref "IC3") (pin "2") (pinfunction "A0_2") (pintype "bidirectional"))
      (node (ref "IC3") (pin "24") (pinfunction "GND_24") (pintype "bidirectional"))
      (node (ref "IC3") (pin "3") (pinfunction "A1_3") (pintype "bidirectional"))
      (node (ref "IC3") (pin "4") (pinfunction "A2_4") (pintype "bidirectional"))
      (node (ref "IC3") (pin "5") (pinfunction "A3_5") (pintype "bidirectional"))
      (node (ref "IC4") (pin "10") (pinfunction "GND_10") (pintype "bidirectional"))
      (node (ref "IC4") (pin "19") (pinfunction "GND_19") (pintype "bidirectional"))
      (node (ref "IC4") (pin "24") (pinfunction "GND_24") (pintype "bidirectional"))
      (node (ref "IC4") (pin "3") (pinfunction "A1_3") (pintype "bidirectional"))
      (node (ref "IC4") (pin "4") (pinfunction "A2_4") (pintype "bidirectional"))
      (node (ref "IC4") (pin "5") (pinfunction "A3_5") (pintype "bidirectional"))
      (node (ref "IC5") (pin "12") (pinfunction "VSS_12") (pintype "power_in"))
      (node (ref "IC5") (pin "2") (pinfunction "A1_2") (pintype "input"))
      (node (ref "IC5") (pin "3") (pinfunction "A2_3") (pintype "input"))
      (node (ref "IC6") (pin "12") (pinfunction "VSS_12") (pintype "power_in"))
      (node (ref "IC6") (pin "2") (pinfunction "A1_2") (pintype "input"))
      (node (ref "IC6") (pin "21") (pinfunction "A0_21") (pintype "input"))
      (node (ref "IC6") (pin "3") (pinfunction "A2_3") (pintype "input"))
      (node (ref "IC7") (pin "4") (pinfunction "GND_4") (pintype "power_in"))
      (node (ref "IC8") (pin "15") (pinfunction "OSC_15") (pintype "input"))
      (node (ref "IC8") (pin "16") (pinfunction "A0_16") (pintype "input"))
      (node (ref "IC8") (pin "17") (pinfunction "A1_17") (pintype "input"))
      (node (ref "IC8") (pin "18") (pinfunction "A2_18") (pintype "input"))
      (node (ref "IC8") (pin "19") (pinfunction "SA0_19") (pintype "input"))
      (node (ref "IC8") (pin "20") (pinfunction "VSS_20") (pintype "power_in"))
      (node (ref "IC9") (pin "4") (pinfunction "GND_4") (pintype "power_in"))
      (node (ref "IC9") (pin "6") (pinfunction "RL_6") (pintype "bidirectional"))
      (node (ref "LOCH1") (pin "B3,0") (pinfunction "MOUNT_B3,0") (pintype "passive"))
      (node (ref "LOCH2") (pin "B3,0") (pinfunction "MOUNT_B3,0") (pintype "passive"))
      (node (ref "R10") (pin "1") (pinfunction "1_1") (pintype "passive"))
      (node (ref "R16") (pin "1") (pinfunction "1_1") (pintype "passive"))
      (node (ref "R20") (pin "1") (pinfunction "1_1") (pintype "passive"))
      (node (ref "R23") (pin "1") (pinfunction "1_1") (pintype "passive"))
      (node (ref "R29") (pin "1") (pinfunction "1_1") (pintype "passive"))
      (node (ref "R3") (pin "1") (pinfunction "1_1") (pintype "passive"))
      (node (ref "R30") (pin "1") (pinfunction "1_1") (pintype "passive"))
      (node (ref "R31") (pin "2") (pinfunction "2_2") (pintype "passive"))
      (node (ref "R6") (pin "2") (pinfunction "2_2") (pintype "passive"))
      (node (ref "RF-POWER") (pin "1") (pinfunction "E_1") (pintype "passive"))
      (node (ref "RF-POWER") (pin "4") (pinfunction "P$1_4") (pintype "power_in"))
      (node (ref "RF-POWER") (pin "5") (pinfunction "P$2_5") (pintype "power_in"))
      (node (ref "SQUELCH") (pin "1") (pinfunction "E_1") (pintype "passive"))
      (node (ref "SQUELCH") (pin "4") (pinfunction "P$1_4") (pintype "power_in"))
      (node (ref "SQUELCH") (pin "5") (pinfunction "P$2_5") (pintype "power_in"))
      (node (ref "SW01") (pin "1") (pinfunction "1_1") (pintype "passive"))
      (node (ref "SW01") (pin "2") (pinfunction "2_2") (pintype "passive"))
      (node (ref "SW02") (pin "1") (pinfunction "1_1") (pintype "passive"))
      (node (ref "SW02") (pin "2") (pinfunction "2_2") (pintype "passive"))
      (node (ref "SW03") (pin "1") (pinfunction "1_1") (pintype "passive"))
      (node (ref "SW03") (pin "2") (pinfunction "2_2") (pintype "passive"))
      (node (ref "SW04") (pin "1") (pinfunction "1_1") (pintype "passive"))
      (node (ref "SW04") (pin "2") (pinfunction "2_2") (pintype "passive"))
      (node (ref "SW05") (pin "1") (pinfunction "1_1") (pintype "passive"))
      (node (ref "SW05") (pin "2") (pinfunction "2_2") (pintype "passive"))
      (node (ref "SW06") (pin "1") (pinfunction "1_1") (pintype "passive"))
      (node (ref "SW06") (pin "2") (pinfunction "2_2") (pintype "passive"))
      (node (ref "SW07") (pin "1") (pinfunction "1_1") (pintype "passive"))
      (node (ref "SW07") (pin "2") (pinfunction "2_2") (pintype "passive"))
      (node (ref "SW08") (pin "1") (pinfunction "1_1") (pintype "passive"))
      (node (ref "SW08") (pin "2") (pinfunction "2_2") (pintype "passive"))
      (node (ref "SW09") (pin "1") (pinfunction "1_1") (pintype "passive"))
      (node (ref "SW09") (pin "2") (pinfunction "2_2") (pintype "passive"))
      (node (ref "SW10") (pin "1") (pinfunction "1_1") (pintype "passive"))
      (node (ref "SW10") (pin "2") (pinfunction "2_2") (pintype "passive"))
      (node (ref "SW11") (pin "1") (pinfunction "1_1") (pintype "passive"))
      (node (ref "SW11") (pin "2") (pinfunction "2_2") (pintype "passive"))
      (node (ref "SW12") (pin "1") (pinfunction "1_1") (pintype "passive"))
      (node (ref "SW12") (pin "2") (pinfunction "2_2") (pintype "passive"))
      (node (ref "SW13") (pin "1") (pinfunction "1_1") (pintype "passive"))
      (node (ref "SW13") (pin "2") (pinfunction "2_2") (pintype "passive"))
      (node (ref "SW14") (pin "1") (pinfunction "1_1") (pintype "passive"))
      (node (ref "SW14") (pin "2") (pinfunction "2_2") (pintype "passive"))
      (node (ref "SW15") (pin "1") (pinfunction "1_1") (pintype "passive"))
      (node (ref "SW15") (pin "2") (pinfunction "2_2") (pintype "passive"))
      (node (ref "SW16") (pin "1") (pinfunction "1_1") (pintype "passive"))
      (node (ref "SW16") (pin "2") (pinfunction "2_2") (pintype "passive"))
      (node (ref "SW17") (pin "1") (pinfunction "1_1") (pintype "passive"))
      (node (ref "SW17") (pin "2") (pinfunction "2_2") (pintype "passive"))
      (node (ref "SW18") (pin "1") (pinfunction "1_1") (pintype "passive"))
      (node (ref "SW18") (pin "2") (pinfunction "2_2") (pintype "passive"))
      (node (ref "SW19") (pin "1") (pinfunction "1_1") (pintype "passive"))
      (node (ref "SW19") (pin "2") (pinfunction "2_2") (pintype "passive"))
      (node (ref "SW20") (pin "1") (pinfunction "1_1") (pintype "passive"))
      (node (ref "SW20") (pin "2") (pinfunction "2_2") (pintype "passive"))
      (node (ref "SW21") (pin "1") (pinfunction "1_1") (pintype "passive"))
      (node (ref "SW21") (pin "2") (pinfunction "2_2") (pintype "passive"))
      (node (ref "SW22") (pin "C") (pinfunction "C_C") (pintype "passive"))
      (node (ref "SW22") (pin "GND@1") (pinfunction "GND_GND@1") (pintype "power_in"))
      (node (ref "SW22") (pin "GND@2") (pinfunction "GND_GND@2") (pintype "power_in"))
      (node (ref "SW22") (pin "GND@3") (pinfunction "GND_GND@3") (pintype "power_in"))
      (node (ref "SW22") (pin "GND@4") (pinfunction "GND_GND@4") (pintype "power_in"))
      (node (ref "SW22") (pin "GND@5") (pinfunction "GND_GND@5") (pintype "power_in"))
      (node (ref "SW22") (pin "GND@6") (pinfunction "GND_GND@6") (pintype "power_in"))
      (node (ref "SW22") (pin "GND@7") (pinfunction "GND_GND@7") (pintype "power_in"))
      (node (ref "SW22") (pin "GND@8") (pinfunction "GND_GND@8") (pintype "power_in"))
      (node (ref "SWR/CAL") (pin "1") (pinfunction "E_1") (pintype "passive"))
      (node (ref "SWR/CAL") (pin "4") (pinfunction "P$1_4") (pintype "power_in"))
      (node (ref "SWR/CAL") (pin "5") (pinfunction "P$2_5") (pintype "power_in"))
      (node (ref "T1") (pin "3") (pinfunction "E_3") (pintype "passive"))
      (node (ref "T4") (pin "3") (pinfunction "E_3") (pintype "passive"))
      (node (ref "T5") (pin "C") (pinfunction "C_C") (pintype "passive"))
      (node (ref "T6") (pin "C") (pinfunction "C_C") (pintype "passive"))
      (node (ref "VOLUME") (pin "4") (pinfunction "P$1_4") (pintype "power_in"))
      (node (ref "VOLUME") (pin "5") (pinfunction "P$2_5") (pintype "power_in"))
      (node (ref "X1") (pin "11") (pinfunction "11_11") (pintype "passive"))
      (node (ref "X1") (pin "12") (pinfunction "12_12") (pintype "passive"))
      (node (ref "X1") (pin "2") (pinfunction "2_2") (pintype "passive"))
      (node (ref "X2") (pin "2") (pinfunction "S_2") (pintype "passive"))
      (node (ref "X6") (pin "11") (pinfunction "11_11") (pintype "passive"))
      (node (ref "X6") (pin "12") (pinfunction "12_12") (pintype "passive"))
      (node (ref "X6") (pin "2") (pinfunction "2_2") (pintype "passive"))
      (node (ref "X7") (pin "11") (pinfunction "11_11") (pintype "passive"))
      (node (ref "X7") (pin "12") (pinfunction "12_12") (pintype "passive"))
      (node (ref "X7") (pin "2") (pinfunction "2_2") (pintype "passive"))
    )
    (net (code "10") (name "Net-(C1-Pad1)") (class "Default")
      (node (ref "C1") (pin "1") (pinfunction "1_1") (pintype "passive"))
      (node (ref "C2") (pin "2") (pinfunction "2_2") (pintype "passive"))
      (node (ref "R28") (pin "2") (pinfunction "2_2") (pintype "passive"))
    )
    (net (code "11") (name "Net-(C1-Pad2)") (class "Default")
      (node (ref "C1") (pin "2") (pinfunction "2_2") (pintype "passive"))
      (node (ref "X6") (pin "5") (pinfunction "5_5") (pintype "passive"))
    )
    (net (code "12") (name "Net-(C4-Pad-)") (class "Default")
      (node (ref "C4") (pin "-") (pinfunction "-_-") (pintype "passive"))
      (node (ref "R15") (pin "2") (pinfunction "2_2") (pintype "passive"))
      (node (ref "R31") (pin "1") (pinfunction "1_1") (pintype "passive"))
    )
    (net (code "13") (name "Net-(C25-Pad2)") (class "Default")
      (node (ref "C25") (pin "2") (pinfunction "2_2") (pintype "passive"))
      (node (ref "D1") (pin "A") (pinfunction "A_A") (pintype "passive"))
      (node (ref "D2") (pin "A") (pinfunction "A_A") (pintype "passive"))
      (node (ref "D3") (pin "A") (pinfunction "A_A") (pintype "passive"))
      (node (ref "X6") (pin "1") (pinfunction "1_1") (pintype "passive"))
    )
    (net (code "14") (name "Net-(C32-Pad2)") (class "Default")
      (node (ref "C32") (pin "2") (pinfunction "2_2") (pintype "passive"))
      (node (ref "R2") (pin "2") (pinfunction "2_2") (pintype "passive"))
      (node (ref "R4") (pin "2") (pinfunction "2_2") (pintype "passive"))
      (node (ref "X7") (pin "6") (pinfunction "6_6") (pintype "passive"))
    )
    (net (code "15") (name "Net-(CLARIFIER-A)") (class "Default")
      (node (ref "CLARIFIER") (pin "3") (pinfunction "A_3") (pintype "passive"))
      (node (ref "R6") (pin "1") (pinfunction "1_1") (pintype "passive"))
    )
    (net (code "16") (name "Net-(CLARIFIER-E)") (class "Default")
      (node (ref "CLARIFIER") (pin "1") (pinfunction "E_1") (pintype "passive"))
      (node (ref "R5") (pin "1") (pinfunction "1_1") (pintype "passive"))
    )
    (net (code "17") (name "Net-(CLARIFIER-S)") (class "Default")
      (node (ref "CLARIFIER") (pin "2") (pinfunction "S_2") (pintype "passive"))
      (node (ref "X7") (pin "4") (pinfunction "4_4") (pintype "passive"))
    )
    (net (code "18") (name "Net-(D4-PadC)") (class "Default")
      (node (ref "D4") (pin "C") (pinfunction "C_C") (pintype "passive"))
      (node (ref "R4") (pin "1") (pinfunction "1_1") (pintype "passive"))
      (node (ref "R5") (pin "2") (pinfunction "2_2") (pintype "passive"))
    )
    (net (code "19") (name "Net-(DISPLAY1-D1_A)") (class "Default")
      (node (ref "C15") (pin "+") (pinfunction "+_+") (pintype "passive"))
      (node (ref "C19") (pin "2") (pinfunction "2_2") (pintype "passive"))
      (node (ref "C33") (pin "+") (pinfunction "+_+") (pintype "passive"))
      (node (ref "C34") (pin "+") (pinfunction "+_+") (pintype "passive"))
      (node (ref "DISPLAY1") (pin "A1") (pinfunction "D1_A_A1") (pintype "input"))
      (node (ref "DISPLAY1") (pin "A2") (pinfunction "D2_A_A2") (pintype "input"))
      (node (ref "DISPLAY1") (pin "A3") (pinfunction "D3_A_A3") (pintype "input"))
      (node (ref "DISPLAY1") (pin "A4") (pinfunction "D4_A_A4") (pintype "input"))
      (node (ref "IC2") (pin "8") (pinfunction "V+_8") (pintype "power_in"))
      (node (ref "LED01") (pin "A") (pinfunction "A_A") (pintype "passive"))
      (node (ref "LED02") (pin "A") (pinfunction "A_A") (pintype "passive"))
      (node (ref "LED03") (pin "A") (pinfunction "A_A") (pintype "passive"))
      (node (ref "LED04") (pin "A") (pinfunction "A_A") (pintype "passive"))
      (node (ref "LED05") (pin "A") (pinfunction "A_A") (pintype "passive"))
      (node (ref "LED06") (pin "A") (pinfunction "A_A") (pintype "passive"))
      (node (ref "LED07") (pin "A") (pinfunction "A_A") (pintype "passive"))
      (node (ref "LED08") (pin "A") (pinfunction "A_A") (pintype "passive"))
      (node (ref "LED09") (pin "A") (pinfunction "A_A") (pintype "passive"))
      (node (ref "LED10") (pin "A") (pinfunction "A_A") (pintype "passive"))
      (node (ref "LED11") (pin "A") (pinfunction "A_A") (pintype "passive"))
      (node (ref "LED12") (pin "A") (pinfunction "A_A") (pintype "passive"))
      (node (ref "LED13") (pin "A") (pinfunction "A_A") (pintype "passive"))
      (node (ref "LED14") (pin "A") (pinfunction "A_A") (pintype "passive"))
      (node (ref "LED15") (pin "A") (pinfunction "A_A") (pintype "passive"))
      (node (ref "LED16") (pin "A") (pinfunction "A_A") (pintype "passive"))
      (node (ref "LED17") (pin "A") (pinfunction "A_A") (pintype "passive"))
      (node (ref "LED18") (pin "A") (pinfunction "A_A") (pintype "passive"))
      (node (ref "LED19") (pin "A") (pinfunction "A_A") (pintype "passive"))
      (node (ref "LED20") (pin "A") (pinfunction "A_A") (pintype "passive"))
      (node (ref "R17") (pin "2") (pinfunction "2_2") (pintype "passive"))
      (node (ref "R18") (pin "2") (pinfunction "2_2") (pintype "passive"))
      (node (ref "X6") (pin "4") (pinfunction "4_4") (pintype "passive"))
    )
    (net (code "20") (name "Net-(DISPLAY1-D1_K)") (class "Default")
      (node (ref "DISPLAY1") (pin "K1") (pinfunction "D1_K_K1") (pintype "input"))
      (node (ref "IC3") (pin "17") (pinfunction "/OUT10_17") (pintype "bidirectional"))
    )
    (net (code "21") (name "Net-(DISPLAY1-D2_K)") (class "Default")
      (node (ref "DISPLAY1") (pin "K2") (pinfunction "D2_K_K2") (pintype "input"))
      (node (ref "IC3") (pin "18") (pinfunction "/OUT11_18") (pintype "bidirectional"))
    )
    (net (code "22") (name "Net-(DISPLAY1-D3_K)") (class "Default")
      (node (ref "DISPLAY1") (pin "K3") (pinfunction "D3_K_K3") (pintype "input"))
      (node (ref "IC4") (pin "17") (pinfunction "/OUT10_17") (pintype "bidirectional"))
    )
    (net (code "23") (name "Net-(DISPLAY1-D4_K)") (class "Default")
      (node (ref "DISPLAY1") (pin "K4") (pinfunction "D4_K_K4") (pintype "input"))
      (node (ref "IC4") (pin "18") (pinfunction "/OUT11_18") (pintype "bidirectional"))
    )
    (net (code "24") (name "Net-(IC1-(A11)PC3)") (class "Default")
      (node (ref "C29") (pin "2") (pinfunction "2_2") (pintype "passive"))
      (node (ref "IC1") (pin "38") (pinfunction "(A11)PC3_38") (pintype "output"))
      (node (ref "X3") (pin "2") (pinfunction "S_2") (pintype "passive"))
    )
    (net (code "25") (name "Net-(IC1-(A12)PC4)") (class "Default")
      (node (ref "C28") (pin "2") (pinfunction "2_2") (pintype "passive"))
      (node (ref "IC1") (pin "39") (pinfunction "(A12)PC4_39") (pintype "output"))
      (node (ref "X3") (pin "1") (pinfunction "S_1") (pintype "passive"))
    )
    (net (code "26") (name "Net-(IC1-(AD2)PA2)") (class "Default")
      (node (ref "C26") (pin "2") (pinfunction "2_2") (pintype "passive"))
      (node (ref "IC1") (pin "49") (pinfunction "(AD2)PA2_49") (pintype "bidirectional"))
      (node (ref "R29") (pin "2") (pinfunction "2_2") (pintype "passive"))
      (node (ref "X6") (pin "6") (pinfunction "6_6") (pintype "passive"))
    )
    (net (code "27") (name "Net-(IC1-(AD3)PA3)") (class "Default")
      (node (ref "C11") (pin "2") (pinfunction "2_2") (pintype "passive"))
      (node (ref "IC1") (pin "48") (pinfunction "(AD3)PA3_48") (pintype "bidirectional"))
      (node (ref "X6") (pin "8") (pinfunction "8_8") (pintype "passive"))
    )
    (net (code "28") (name "Net-(IC1-(AD4)PA4)") (class "Default")
      (node (ref "C12") (pin "2") (pinfunction "2_2") (pintype "passive"))
      (node (ref "IC1") (pin "47") (pinfunction "(AD4)PA4_47") (pintype "bidirectional"))
      (node (ref "X6") (pin "10") (pinfunction "10_10") (pintype "passive"))
    )
    (net (code "29") (name "Net-(IC1-(AD5)PA5)") (class "Default")
      (node (ref "C10") (pin "2") (pinfunction "2_2") (pintype "passive"))
      (node (ref "IC1") (pin "46") (pinfunction "(AD5)PA5_46") (pintype "bidirectional"))
      (node (ref "X6") (pin "9") (pinfunction "9_9") (pintype "passive"))
    )
    (net (code "30") (name "Net-(IC1-(AD6)PA6)") (class "Default")
      (node (ref "C9") (pin "2") (pinfunction "2_2") (pintype "passive"))
      (node (ref "IC1") (pin "45") (pinfunction "(AD6)PA6_45") (pintype "bidirectional"))
      (node (ref "X6") (pin "7") (pinfunction "7_7") (pintype "passive"))
    )
    (net (code "31") (name "Net-(IC1-(AD7)PA7)") (class "Default")
      (node (ref "IC1") (pin "44") (pinfunction "(AD7)PA7_44") (pintype "bidirectional"))
      (node (ref "R12") (pin "1") (pinfunction "1_1") (pintype "passive"))
    )
    (net (code "32") (name "Net-(IC1-(IC3{slash}INT7)PE7)") (class "Default")
      (node (ref "C3") (pin "+") (pinfunction "+_+") (pintype "passive"))
      (node (ref "IC1") (pin "9") (pinfunction "(IC3/INT7)PE7_9") (pintype "bidirectional"))
      (node (ref "R25") (pin "1") (pinfunction "1_1") (pintype "passive"))
    )
    (net (code "33") (name "Net-(IC1-(MISO)PB3)") (class "Default")
      (node (ref "IC1") (pin "13") (pinfunction "(MISO)PB3_13") (pintype "bidirectional"))
      (node (ref "IC7") (pin "2") (pinfunction "SO_2") (pintype "bidirectional"))
    )
    (net (code "34") (name "Net-(IC1-(MOSI)PB2)") (class "Default")
      (node (ref "IC1") (pin "12") (pinfunction "(MOSI)PB2_12") (pintype "bidirectional"))
      (node (ref "IC7") (pin "5") (pinfunction "SI_5") (pintype "input"))
    )
    (net (code "35") (name "Net-(IC1-(OC1A)PB5)") (class "Default")
      (node (ref "IC1") (pin "15") (pinfunction "(OC1A)PB5_15") (pintype "bidirectional"))
      (node (ref "IC9") (pin "5") (pinfunction "RW_5") (pintype "bidirectional"))
    )
    (net (code "36") (name "Net-(IC1-(OC3B{slash}INT4)PE4)") (class "Default")
      (node (ref "C31") (pin "1") (pinfunction "1_1") (pintype "passive"))
      (node (ref "D3") (pin "C") (pinfunction "C_C") (pintype "passive"))
      (node (ref "IC1") (pin "6") (pinfunction "(OC3B/INT4)PE4_6") (pintype "bidirectional"))
      (node (ref "R23") (pin "2") (pinfunction "2_2") (pintype "passive"))
    )
    (net (code "37") (name "Net-(IC1-(OC3C{slash}INT5)PE5)") (class "Default")
      (node (ref "IC1") (pin "7") (pinfunction "(OC3C/INT5)PE5_7") (pintype "bidirectional"))
      (node (ref "SW01") (pin "3") (pinfunction "3_3") (pintype "passive"))
      (node (ref "SW01") (pin "4") (pinfunction "4_4") (pintype "passive"))
    )
    (net (code "38") (name "Net-(IC1-(SS)PB0)") (class "Default")
      (node (ref "IC1") (pin "10") (pinfunction "(SS)PB0_10") (pintype "bidirectional"))
      (node (ref "IC7") (pin "1") (pinfunction "~{CS}_1") (pintype "input"))
    )
    (net (code "39") (name "Net-(IC1-(T3{slash}INT6)PE6)") (class "Default")
      (node (ref "C30") (pin "1") (pinfunction "1_1") (pintype "passive"))
      (node (ref "IC1") (pin "8") (pinfunction "(T3/INT6)PE6_8") (pintype "bidirectional"))
      (node (ref "X3") (pin "4") (pinfunction "S_4") (pintype "passive"))
    )
    (net (code "40") (name "Net-(IC1-(XCK0{slash}AIN0)PE2)") (class "Default")
      (node (ref "IC1") (pin "4") (pinfunction "(XCK0/AIN0)PE2_4") (pintype "bidirectional"))
      (node (ref "X3") (pin "3") (pinfunction "S_3") (pintype "passive"))
    )
    (net (code "41") (name "Net-(IC1-AVCC)") (class "Default")
      (node (ref "C7") (pin "2") (pinfunction "2_2") (pintype "passive"))
      (node (ref "IC1") (pin "64") (pinfunction "AVCC_64") (pintype "power_in"))
      (node (ref "L1") (pin "1") (pinfunction "1_1") (pintype "passive"))
    )
    (net (code "42") (name "Net-(IC1-PF1(ADC1))") (class "Default")
      (node (ref "IC1") (pin "60") (pinfunction "PF1(ADC1)_60") (pintype "input"))
      (node (ref "SWR/CAL") (pin "3") (pinfunction "A_3") (pintype "passive"))
      (node (ref "X7") (pin "1") (pinfunction "1_1") (pintype "passive"))
    )
    (net (code "43") (name "Net-(IC1-XTAL1)") (class "Default")
      (node (ref "C6") (pin "2") (pinfunction "2_2") (pintype "passive"))
      (node (ref "IC1") (pin "24") (pinfunction "XTAL1_24") (pintype "bidirectional"))
      (node (ref "Q1") (pin "2") (pinfunction "2_2") (pintype "passive"))
    )
    (net (code "44") (name "Net-(IC1-XTAL2)") (class "Default")
      (node (ref "C5") (pin "2") (pinfunction "2_2") (pintype "passive"))
      (node (ref "IC1") (pin "23") (pinfunction "XTAL2_23") (pintype "bidirectional"))
      (node (ref "Q1") (pin "1") (pinfunction "1_1") (pintype "passive"))
    )
    (net (code "45") (name "Net-(IC2A-+IN)") (class "Default")
      (node (ref "C20") (pin "2") (pinfunction "2_2") (pintype "passive"))
      (node (ref "IC2") (pin "3") (pinfunction "+IN_3") (pintype "input"))
      (node (ref "IC2") (pin "6") (pinfunction "-IN_6") (pintype "input"))
      (node (ref "R10") (pin "2") (pinfunction "2_2") (pintype "passive"))
      (node (ref "R17") (pin "1") (pinfunction "1_1") (pintype "passive"))
      (node (ref "X5") (pin "1") (pinfunction "S_1") (pintype "passive"))
    )
    (net (code "46") (name "Net-(IC2A--IN)") (class "Default")
      (node (ref "IC2") (pin "2") (pinfunction "-IN_2") (pintype "input"))
      (node (ref "R18") (pin "1") (pinfunction "1_1") (pintype "passive"))
      (node (ref "R19") (pin "2") (pinfunction "2_2") (pintype "passive"))
    )
    (net (code "47") (name "Net-(IC2A-OUT)") (class "Default")
      (node (ref "IC2") (pin "1") (pinfunction "OUT_1") (pintype "output"))
      (node (ref "R11") (pin "2") (pinfunction "2_2") (pintype "passive"))
      (node (ref "R21") (pin "2") (pinfunction "2_2") (pintype "passive"))
    )
    (net (code "48") (name "Net-(IC2B-+IN)") (class "Default")
      (node (ref "IC2") (pin "5") (pinfunction "+IN_5") (pintype "input"))
      (node (ref "R19") (pin "1") (pinfunction "1_1") (pintype "passive"))
      (node (ref "R20") (pin "2") (pinfunction "2_2") (pintype "passive"))
    )
    (net (code "49") (name "Net-(IC2B-OUT)") (class "Default")
      (node (ref "IC2") (pin "7") (pinfunction "OUT_7") (pintype "output"))
      (node (ref "R1") (pin "2") (pinfunction "2_2") (pintype "passive"))
      (node (ref "R22") (pin "2") (pinfunction "2_2") (pintype "passive"))
    )
    (net (code "50") (name "Net-(IC3-REXT)") (class "Default")
      (node (ref "IC3") (pin "1") (pinfunction "REXT_1") (pintype "bidirectional"))
      (node (ref "R3") (pin "2") (pinfunction "2_2") (pintype "passive"))
    )
    (net (code "51") (name "Net-(IC3-{slash}OUT0)") (class "Default")
      (node (ref "IC3") (pin "6") (pinfunction "/OUT0_6") (pintype "bidirectional"))
      (node (ref "LED07") (pin "C") (pinfunction "C_C") (pintype "passive"))
    )
    (net (code "52") (name "Net-(IC3-{slash}OUT1)") (class "Default")
      (node (ref "IC3") (pin "7") (pinfunction "/OUT1_7") (pintype "bidirectional"))
      (node (ref "LED08") (pin "C") (pinfunction "C_C") (pintype "passive"))
    )
    (net (code "53") (name "Net-(IC3-{slash}OUT2)") (class "Default")
      (node (ref "IC3") (pin "8") (pinfunction "/OUT2_8") (pintype "bidirectional"))
      (node (ref "LED05") (pin "C") (pinfunction "C_C") (pintype "passive"))
    )
    (net (code "54") (name "Net-(IC3-{slash}OUT3)") (class "Default")
      (node (ref "IC3") (pin "9") (pinfunction "/OUT3_9") (pintype "bidirectional"))
      (node (ref "LED06") (pin "C") (pinfunction "C_C") (pintype "passive"))
    )
    (net (code "55") (name "Net-(IC3-{slash}OUT4)") (class "Default")
      (node (ref "IC3") (pin "11") (pinfunction "/OUT4_11") (pintype "bidirectional"))
      (node (ref "LED03") (pin "C") (pinfunction "C_C") (pintype "passive"))
    )
    (net (code "56") (name "Net-(IC3-{slash}OUT5)") (class "Default")
      (node (ref "IC3") (pin "12") (pinfunction "/OUT5_12") (pintype "bidirectional"))
      (node (ref "LED04") (pin "C") (pinfunction "C_C") (pintype "passive"))
    )
    (net (code "57") (name "Net-(IC3-{slash}OUT6)") (class "Default")
      (node (ref "IC3") (pin "13") (pinfunction "/OUT6_13") (pintype "bidirectional"))
      (node (ref "LED01") (pin "C") (pinfunction "C_C") (pintype "passive"))
    )
    (net (code "58") (name "Net-(IC3-{slash}OUT7)") (class "Default")
      (node (ref "IC3") (pin "14") (pinfunction "/OUT7_14") (pintype "bidirectional"))
      (node (ref "LED02") (pin "C") (pinfunction "C_C") (pintype "passive"))
    )
    (net (code "59") (name "Net-(IC3-{slash}OUT8)") (class "Default")
      (node (ref "IC3") (pin "15") (pinfunction "/OUT8_15") (pintype "bidirectional"))
      (node (ref "LED09") (pin "C") (pinfunction "C_C") (pintype "passive"))
    )
    (net (code "60") (name "Net-(IC3-{slash}OUT9)") (class "Default")
      (node (ref "IC3") (pin "16") (pinfunction "/OUT9_16") (pintype "bidirectional"))
      (node (ref "LED10") (pin "C") (pinfunction "C_C") (pintype "passive"))
    )
    (net (code "61") (name "Net-(IC3-{slash}RESET)") (class "Default")
      (node (ref "IC3") (pin "25") (pinfunction "/RESET_25") (pintype "bidirectional"))
      (node (ref "R13") (pin "2") (pinfunction "2_2") (pintype "passive"))
    )
    (net (code "62") (name "Net-(IC4-REXT)") (class "Default")
      (node (ref "IC4") (pin "1") (pinfunction "REXT_1") (pintype "bidirectional"))
      (node (ref "R16") (pin "2") (pinfunction "2_2") (pintype "passive"))
    )
    (net (code "63") (name "Net-(IC4-{slash}OUT0)") (class "Default")
      (node (ref "IC4") (pin "6") (pinfunction "/OUT0_6") (pintype "bidirectional"))
      (node (ref "LED17") (pin "C") (pinfunction "C_C") (pintype "passive"))
    )
    (net (code "64") (name "Net-(IC4-{slash}OUT1)") (class "Default")
      (node (ref "IC4") (pin "7") (pinfunction "/OUT1_7") (pintype "bidirectional"))
      (node (ref "LED18") (pin "C") (pinfunction "C_C") (pintype "passive"))
    )
    (net (code "65") (name "Net-(IC4-{slash}OUT2)") (class "Default")
      (node (ref "IC4") (pin "8") (pinfunction "/OUT2_8") (pintype "bidirectional"))
      (node (ref "LED15") (pin "C") (pinfunction "C_C") (pintype "passive"))
    )
    (net (code "66") (name "Net-(IC4-{slash}OUT3)") (class "Default")
      (node (ref "IC4") (pin "9") (pinfunction "/OUT3_9") (pintype "bidirectional"))
      (node (ref "LED16") (pin "C") (pinfunction "C_C") (pintype "passive"))
    )
    (net (code "67") (name "Net-(IC4-{slash}OUT4)") (class "Default")
      (node (ref "IC4") (pin "11") (pinfunction "/OUT4_11") (pintype "bidirectional"))
      (node (ref "LED11") (pin "C") (pinfunction "C_C") (pintype "passive"))
    )
    (net (code "68") (name "Net-(IC4-{slash}OUT5)") (class "Default")
      (node (ref "IC4") (pin "12") (pinfunction "/OUT5_12") (pintype "bidirectional"))
      (node (ref "LED12") (pin "C") (pinfunction "C_C") (pintype "passive"))
    )
    (net (code "69") (name "Net-(IC4-{slash}OUT6)") (class "Default")
      (node (ref "IC4") (pin "13") (pinfunction "/OUT6_13") (pintype "bidirectional"))
      (node (ref "LED13") (pin "C") (pinfunction "C_C") (pintype "passive"))
    )
    (net (code "70") (name "Net-(IC4-{slash}OUT7)") (class "Default")
      (node (ref "IC4") (pin "14") (pinfunction "/OUT7_14") (pintype "bidirectional"))
      (node (ref "LED14") (pin "C") (pinfunction "C_C") (pintype "passive"))
    )
    (net (code "71") (name "Net-(IC4-{slash}OUT8)") (class "Default")
      (node (ref "IC4") (pin "15") (pinfunction "/OUT8_15") (pintype "bidirectional"))
      (node (ref "LED19") (pin "C") (pinfunction "C_C") (pintype "passive"))
    )
    (net (code "72") (name "Net-(IC4-{slash}OUT9)") (class "Default")
      (node (ref "IC4") (pin "16") (pinfunction "/OUT9_16") (pintype "bidirectional"))
      (node (ref "LED20") (pin "C") (pinfunction "C_C") (pintype "passive"))
    )
    (net (code "73") (name "Net-(IC4-{slash}RESET)") (class "Default")
      (node (ref "IC4") (pin "25") (pinfunction "/RESET_25") (pintype "bidirectional"))
      (node (ref "R33") (pin "2") (pinfunction "2_2") (pintype "passive"))
    )
    (net (code "74") (name "Net-(IC5-I{slash}O0.0)") (class "Default")
      (node (ref "IC5") (pin "4") (pinfunction "I/O0.0_4") (pintype "bidirectional"))
      (node (ref "SW13") (pin "3") (pinfunction "3_3") (pintype "passive"))
      (node (ref "SW13") (pin "4") (pinfunction "4_4") (pintype "passive"))
    )
    (net (code "75") (name "Net-(IC5-I{slash}O0.1)") (class "Default")
      (node (ref "IC5") (pin "5") (pinfunction "I/O0.1_5") (pintype "bidirectional"))
      (node (ref "SW14") (pin "3") (pinfunction "3_3") (pintype "passive"))
      (node (ref "SW14") (pin "4") (pinfunction "4_4") (pintype "passive"))
    )
    (net (code "76") (name "Net-(IC5-I{slash}O0.2)") (class "Default")
      (node (ref "IC5") (pin "6") (pinfunction "I/O0.2_6") (pintype "bidirectional"))
      (node (ref "SW15") (pin "3") (pinfunction "3_3") (pintype "passive"))
      (node (ref "SW15") (pin "4") (pinfunction "4_4") (pintype "passive"))
    )
    (net (code "77") (name "Net-(IC5-I{slash}O0.6)") (class "Default")
      (node (ref "IC5") (pin "10") (pinfunction "I/O0.6_10") (pintype "bidirectional"))
      (node (ref "T5") (pin "E") (pinfunction "E_E") (pintype "passive"))
    )
    (net (code "78") (name "Net-(IC5-I{slash}O0.7)") (class "Default")
      (node (ref "IC5") (pin "11") (pinfunction "I/O0.7_11") (pintype "bidirectional"))
      (node (ref "T6") (pin "E") (pinfunction "E_E") (pintype "passive"))
    )
    (net (code "79") (name "Net-(IC5-I{slash}O1.0)") (class "Default")
      (node (ref "IC5") (pin "13") (pinfunction "I/O1.0_13") (pintype "bidirectional"))
      (node (ref "SW17") (pin "3") (pinfunction "3_3") (pintype "passive"))
      (node (ref "SW17") (pin "4") (pinfunction "4_4") (pintype "passive"))
    )
    (net (code "80") (name "Net-(IC5-I{slash}O1.1)") (class "Default")
      (node (ref "C21") (pin "2") (pinfunction "2_2") (pintype "passive"))
      (node (ref "IC5") (pin "14") (pinfunction "I/O1.1_14") (pintype "bidirectional"))
      (node (ref "SW22") (pin "B") (pinfunction "B_B") (pintype "passive"))
    )
    (net (code "81") (name "Net-(IC5-I{slash}O1.2)") (class "Default")
      (node (ref "C22") (pin "2") (pinfunction "2_2") (pintype "passive"))
      (node (ref "IC5") (pin "15") (pinfunction "I/O1.2_15") (pintype "bidirectional"))
      (node (ref "SW22") (pin "A") (pinfunction "A_A") (pintype "passive"))
    )
    (net (code "82") (name "Net-(IC5-I{slash}O1.3)") (class "Default")
      (node (ref "IC5") (pin "16") (pinfunction "I/O1.3_16") (pintype "bidirectional"))
      (node (ref "SW16") (pin "3") (pinfunction "3_3") (pintype "passive"))
      (node (ref "SW16") (pin "4") (pinfunction "4_4") (pintype "passive"))
    )
    (net (code "83") (name "Net-(IC5-I{slash}O1.4)") (class "Default")
      (node (ref "IC5") (pin "17") (pinfunction "I/O1.4_17") (pintype "bidirectional"))
      (node (ref "SW19") (pin "3") (pinfunction "3_3") (pintype "passive"))
      (node (ref "SW19") (pin "4") (pinfunction "4_4") (pintype "passive"))
    )
    (net (code "84") (name "Net-(IC5-I{slash}O1.5)") (class "Default")
      (node (ref "IC5") (pin "18") (pinfunction "I/O1.5_18") (pintype "bidirectional"))
      (node (ref "SW18") (pin "3") (pinfunction "3_3") (pintype "passive"))
      (node (ref "SW18") (pin "4") (pinfunction "4_4") (pintype "passive"))
    )
    (net (code "85") (name "Net-(IC5-I{slash}O1.6)") (class "Default")
      (node (ref "IC5") (pin "19") (pinfunction "I/O1.6_19") (pintype "bidirectional"))
      (node (ref "SW21") (pin "3") (pinfunction "3_3") (pintype "passive"))
      (node (ref "SW21") (pin "4") (pinfunction "4_4") (pintype "passive"))
    )
    (net (code "86") (name "Net-(IC5-I{slash}O1.7)") (class "Default")
      (node (ref "IC5") (pin "20") (pinfunction "I/O1.7_20") (pintype "bidirectional"))
      (node (ref "SW20") (pin "3") (pinfunction "3_3") (pintype "passive"))
      (node (ref "SW20") (pin "4") (pinfunction "4_4") (pintype "passive"))
    )
    (net (code "87") (name "Net-(IC5-~{INT})") (class "Default")
      (node (ref "IC5") (pin "1") (pinfunction "~{INT}_1") (pintype "output"))
      (node (ref "IC6") (pin "1") (pinfunction "~{INT}_1") (pintype "output"))
      (node (ref "R25") (pin "2") (pinfunction "2_2") (pintype "passive"))
    )
    (net (code "88") (name "Net-(IC6-I{slash}O0.0)") (class "Default")
      (node (ref "IC6") (pin "4") (pinfunction "I/O0.0_4") (pintype "bidirectional"))
      (node (ref "SW12") (pin "3") (pinfunction "3_3") (pintype "passive"))
      (node (ref "SW12") (pin "4") (pinfunction "4_4") (pintype "passive"))
    )
    (net (code "89") (name "Net-(IC6-I{slash}O0.1)") (class "Default")
      (node (ref "IC6") (pin "5") (pinfunction "I/O0.1_5") (pintype "bidirectional"))
      (node (ref "SW11") (pin "3") (pinfunction "3_3") (pintype "passive"))
      (node (ref "SW11") (pin "4") (pinfunction "4_4") (pintype "passive"))
    )
    (net (code "90") (name "Net-(IC6-I{slash}O0.2)") (class "Default")
      (node (ref "IC6") (pin "6") (pinfunction "I/O0.2_6") (pintype "bidirectional"))
      (node (ref "SW10") (pin "3") (pinfunction "3_3") (pintype "passive"))
      (node (ref "SW10") (pin "4") (pinfunction "4_4") (pintype "passive"))
    )
    (net (code "91") (name "Net-(IC6-I{slash}O0.3)") (class "Default")
      (node (ref "IC6") (pin "7") (pinfunction "I/O0.3_7") (pintype "bidirectional"))
      (node (ref "SW02") (pin "3") (pinfunction "3_3") (pintype "passive"))
      (node (ref "SW02") (pin "4") (pinfunction "4_4") (pintype "passive"))
    )
    (net (code "92") (name "Net-(IC6-I{slash}O0.4)") (class "Default")
      (node (ref "IC6") (pin "8") (pinfunction "I/O0.4_8") (pintype "bidirectional"))
      (node (ref "SW03") (pin "3") (pinfunction "3_3") (pintype "passive"))
      (node (ref "SW03") (pin "4") (pinfunction "4_4") (pintype "passive"))
    )
    (net (code "93") (name "Net-(IC6-I{slash}O0.5)") (class "Default")
      (node (ref "IC6") (pin "9") (pinfunction "I/O0.5_9") (pintype "bidirectional"))
      (node (ref "SW04") (pin "3") (pinfunction "3_3") (pintype "passive"))
      (node (ref "SW04") (pin "4") (pinfunction "4_4") (pintype "passive"))
    )
    (net (code "94") (name "Net-(IC6-I{slash}O0.6)") (class "Default")
      (node (ref "IC6") (pin "10") (pinfunction "I/O0.6_10") (pintype "bidirectional"))
      (node (ref "SW05") (pin "3") (pinfunction "3_3") (pintype "passive"))
      (node (ref "SW05") (pin "4") (pinfunction "4_4") (pintype "passive"))
    )
    (net (code "95") (name "Net-(IC6-I{slash}O1.0)") (class "Default")
      (node (ref "IC6") (pin "13") (pinfunction "I/O1.0_13") (pintype "bidirectional"))
      (node (ref "SW06") (pin "3") (pinfunction "3_3") (pintype "passive"))
      (node (ref "SW06") (pin "4") (pinfunction "4_4") (pintype "passive"))
    )
    (net (code "96") (name "Net-(IC6-I{slash}O1.1)") (class "Default")
      (node (ref "IC6") (pin "14") (pinfunction "I/O1.1_14") (pintype "bidirectional"))
      (node (ref "R8") (pin "1") (pinfunction "1_1") (pintype "passive"))
      (node (ref "R9") (pin "2") (pinfunction "2_2") (pintype "passive"))
    )
    (net (code "97") (name "Net-(IC6-I{slash}O1.2)") (class "Default")
      (node (ref "IC6") (pin "15") (pinfunction "I/O1.2_15") (pintype "bidirectional"))
      (node (ref "SW07") (pin "3") (pinfunction "3_3") (pintype "passive"))
      (node (ref "SW07") (pin "4") (pinfunction "4_4") (pintype "passive"))
    )
    (net (code "98") (name "Net-(IC6-I{slash}O1.3)") (class "Default")
      (node (ref "IC6") (pin "16") (pinfunction "I/O1.3_16") (pintype "bidirectional"))
      (node (ref "SW08") (pin "3") (pinfunction "3_3") (pintype "passive"))
      (node (ref "SW08") (pin "4") (pinfunction "4_4") (pintype "passive"))
    )
    (net (code "99") (name "Net-(IC6-I{slash}O1.4)") (class "Default")
      (node (ref "IC6") (pin "17") (pinfunction "I/O1.4_17") (pintype "bidirectional"))
      (node (ref "SW09") (pin "3") (pinfunction "3_3") (pintype "passive"))
      (node (ref "SW09") (pin "4") (pinfunction "4_4") (pintype "passive"))
    )
    (net (code "100") (name "Net-(IC8-BP0)") (class "Default")
      (node (ref "DISPLAY1") (pin "COM1") (pinfunction "COM1_COM1") (pintype "input"))
      (node (ref "IC8") (pin "25") (pinfunction "BP0_25") (pintype "output"))
    )
    (net (code "101") (name "Net-(IC8-BP1)") (class "Default")
      (node (ref "DISPLAY1") (pin "COM2") (pinfunction "COM2_COM2") (pintype "input"))
      (node (ref "IC8") (pin "26") (pinfunction "BP1_26") (pintype "output"))
    )
    (net (code "102") (name "Net-(IC8-BP2)") (class "Default")
      (node (ref "DISPLAY1") (pin "COM3") (pinfunction "COM3_COM3") (pintype "input"))
      (node (ref "IC8") (pin "27") (pinfunction "BP2_27") (pintype "output"))
    )
    (net (code "103") (name "Net-(IC8-S0)") (class "Default")
      (node (ref "DISPLAY1") (pin "SEG01") (pinfunction "SEG01_SEG01") (pintype "input"))
      (node (ref "IC8") (pin "29") (pinfunction "S0_29") (pintype "output"))
    )
    (net (code "104") (name "Net-(IC8-S1)") (class "Default")
      (node (ref "DISPLAY1") (pin "SEG02") (pinfunction "SEG02_SEG02") (pintype "input"))
      (node (ref "IC8") (pin "30") (pinfunction "S1_30") (pintype "output"))
    )
    (net (code "105") (name "Net-(IC8-S2)") (class "Default")
      (node (ref "DISPLAY1") (pin "SEG03") (pinfunction "SEG03_SEG03") (pintype "input"))
      (node (ref "IC8") (pin "31") (pinfunction "S2_31") (pintype "output"))
    )
    (net (code "106") (name "Net-(IC8-S3)") (class "Default")
      (node (ref "DISPLAY1") (pin "SEG04") (pinfunction "SEG04_SEG04") (pintype "input"))
      (node (ref "IC8") (pin "32") (pinfunction "S3_32") (pintype "output"))
    )
    (net (code "107") (name "Net-(IC8-S4)") (class "Default")
      (node (ref "DISPLAY1") (pin "SEG05") (pinfunction "SEG05_SEG05") (pintype "input"))
      (node (ref "IC8") (pin "34") (pinfunction "S4_34") (pintype "output"))
    )
    (net (code "108") (name "Net-(IC8-S5)") (class "Default")
      (node (ref "DISPLAY1") (pin "SEG06") (pinfunction "SEG06_SEG06") (pintype "input"))
      (node (ref "IC8") (pin "35") (pinfunction "S5_35") (pintype "output"))
    )
    (net (code "109") (name "Net-(IC8-S6)") (class "Default")
      (node (ref "DISPLAY1") (pin "SEG07") (pinfunction "SEG07_SEG07") (pintype "input"))
      (node (ref "IC8") (pin "36") (pinfunction "S6_36") (pintype "output"))
    )
    (net (code "110") (name "Net-(IC8-S7)") (class "Default")
      (node (ref "DISPLAY1") (pin "SEG08") (pinfunction "SEG08_SEG08") (pintype "input"))
      (node (ref "IC8") (pin "37") (pinfunction "S7_37") (pintype "output"))
    )
    (net (code "111") (name "Net-(IC8-S8)") (class "Default")
      (node (ref "DISPLAY1") (pin "SEG09") (pinfunction "SEG09_SEG09") (pintype "input"))
      (node (ref "IC8") (pin "38") (pinfunction "S8_38") (pintype "output"))
    )
    (net (code "112") (name "Net-(IC8-S9)") (class "Default")
      (node (ref "DISPLAY1") (pin "SEG10") (pinfunction "SEG10_SEG10") (pintype "input"))
      (node (ref "IC8") (pin "39") (pinfunction "S9_39") (pintype "output"))
    )
    (net (code "113") (name "Net-(IC8-S10)") (class "Default")
      (node (ref "DISPLAY1") (pin "SEG11") (pinfunction "SEG11_SEG11") (pintype "input"))
      (node (ref "IC8") (pin "40") (pinfunction "S10_40") (pintype "output"))
    )
    (net (code "114") (name "Net-(IC8-S11)") (class "Default")
      (node (ref "DISPLAY1") (pin "SEG12") (pinfunction "SEG12_SEG12") (pintype "input"))
      (node (ref "IC8") (pin "41") (pinfunction "S11_41") (pintype "output"))
    )
    (net (code "115") (name "Net-(IC8-S12)") (class "Default")
      (node (ref "DISPLAY1") (pin "SEG13") (pinfunction "SEG13_SEG13") (pintype "input"))
      (node (ref "IC8") (pin "42") (pinfunction "S12_42") (pintype "output"))
    )
    (net (code "116") (name "Net-(IC8-S13)") (class "Default")
      (node (ref "DISPLAY1") (pin "SEG14") (pinfunction "SEG14_SEG14") (pintype "input"))
      (node (ref "IC8") (pin "43") (pinfunction "S13_43") (pintype "output"))
    )
    (net (code "117") (name "Net-(IC8-S14)") (class "Default")
      (node (ref "DISPLAY1") (pin "SEG15") (pinfunction "SEG15_SEG15") (pintype "input"))
      (node (ref "IC8") (pin "44") (pinfunction "S14_44") (pintype "output"))
    )
    (net (code "118") (name "Net-(IC8-S15)") (class "Default")
      (node (ref "DISPLAY1") (pin "SEG16") (pinfunction "SEG16_SEG16") (pintype "input"))
      (node (ref "IC8") (pin "45") (pinfunction "S15_45") (pintype "output"))
    )
    (net (code "119") (name "Net-(IC8-S16)") (class "Default")
      (node (ref "DISPLAY1") (pin "SEG17") (pinfunction "SEG17_SEG17") (pintype "input"))
      (node (ref "IC8") (pin "46") (pinfunction "S16_46") (pintype "output"))
    )
    (net (code "120") (name "Net-(IC8-S17)") (class "Default")
      (node (ref "DISPLAY1") (pin "SEG18") (pinfunction "SEG18_SEG18") (pintype "input"))
      (node (ref "IC8") (pin "47") (pinfunction "S17_47") (pintype "output"))
    )
    (net (code "121") (name "Net-(IC8-S18)") (class "Default")
      (node (ref "DISPLAY1") (pin "SEG19") (pinfunction "SEG19_SEG19") (pintype "input"))
      (node (ref "IC8") (pin "49") (pinfunction "S18_49") (pintype "output"))
    )
    (net (code "122") (name "Net-(IC8-S19)") (class "Default")
      (node (ref "DISPLAY1") (pin "SEG20") (pinfunction "SEG20_SEG20") (pintype "input"))
      (node (ref "IC8") (pin "50") (pinfunction "S19_50") (pintype "output"))
    )
    (net (code "123") (name "Net-(IC8-S20)") (class "Default")
      (node (ref "DISPLAY1") (pin "SEG21") (pinfunction "SEG21_SEG21") (pintype "input"))
      (node (ref "IC8") (pin "51") (pinfunction "S20_51") (pintype "output"))
    )
    (net (code "124") (name "Net-(IC8-S21)") (class "Default")
      (node (ref "DISPLAY1") (pin "SEG22") (pinfunction "SEG22_SEG22") (pintype "input"))
      (node (ref "IC8") (pin "52") (pinfunction "S21_52") (pintype "output"))
    )
    (net (code "125") (name "Net-(IC8-S22)") (class "Default")
      (node (ref "DISPLAY1") (pin "SEG23") (pinfunction "SEG23_SEG23") (pintype "input"))
      (node (ref "IC8") (pin "53") (pinfunction "S22_53") (pintype "output"))
    )
    (net (code "126") (name "Net-(IC8-S23)") (class "Default")
      (node (ref "DISPLAY1") (pin "SEG24") (pinfunction "SEG24_SEG24") (pintype "input"))
      (node (ref "IC8") (pin "54") (pinfunction "S23_54") (pintype "output"))
    )
    (net (code "127") (name "Net-(IC8-S24)") (class "Default")
      (node (ref "DISPLAY1") (pin "SEG25") (pinfunction "SEG25_SEG25") (pintype "input"))
      (node (ref "IC8") (pin "55") (pinfunction "S24_55") (pintype "output"))
    )
    (net (code "128") (name "Net-(IC8-S25)") (class "Default")
      (node (ref "DISPLAY1") (pin "SEG26") (pinfunction "SEG26_SEG26") (pintype "input"))
      (node (ref "IC8") (pin "56") (pinfunction "S25_56") (pintype "output"))
    )
    (net (code "129") (name "Net-(IC8-S26)") (class "Default")
      (node (ref "DISPLAY1") (pin "SEG27") (pinfunction "SEG27_SEG27") (pintype "input"))
      (node (ref "IC8") (pin "57") (pinfunction "S26_57") (pintype "output"))
    )
    (net (code "130") (name "Net-(IC8-S27)") (class "Default")
      (node (ref "DISPLAY1") (pin "SEG28") (pinfunction "SEG28_SEG28") (pintype "input"))
      (node (ref "IC8") (pin "58") (pinfunction "S27_58") (pintype "output"))
    )
    (net (code "131") (name "Net-(IC8-S28)") (class "Default")
      (node (ref "DISPLAY1") (pin "SEG29") (pinfunction "SEG29_SEG29") (pintype "input"))
      (node (ref "IC8") (pin "59") (pinfunction "S28_59") (pintype "output"))
    )
    (net (code "132") (name "Net-(IC8-S29)") (class "Default")
      (node (ref "DISPLAY1") (pin "SEG30") (pinfunction "SEG30_SEG30") (pintype "input"))
      (node (ref "IC8") (pin "60") (pinfunction "S29_60") (pintype "output"))
    )
    (net (code "133") (name "Net-(IC8-S30)") (class "Default")
      (node (ref "DISPLAY1") (pin "SEG31") (pinfunction "SEG31_SEG31") (pintype "input"))
      (node (ref "IC8") (pin "61") (pinfunction "S30_61") (pintype "output"))
    )
    (net (code "134") (name "Net-(IC8-S31)") (class "Default")
      (node (ref "DISPLAY1") (pin "SEG32") (pinfunction "SEG32_SEG32") (pintype "input"))
      (node (ref "IC8") (pin "62") (pinfunction "S31_62") (pintype "output"))
    )
    (net (code "135") (name "Net-(IC8-S32)") (class "Default")
      (node (ref "DISPLAY1") (pin "SEG33") (pinfunction "SEG33_SEG33") (pintype "input"))
      (node (ref "IC8") (pin "63") (pinfunction "S32_63") (pintype "output"))
    )
    (net (code "136") (name "Net-(IC8-VLCD)") (class "Default")
      (node (ref "IC8") (pin "21") (pinfunction "VLCD_21") (pintype "power_in"))
      (node (ref "R30") (pin "2") (pinfunction "2_2") (pintype "passive"))
    )
    (net (code "137") (name "Net-(IC9-RH)") (class "Default")
      (node (ref "IC9") (pin "7") (pinfunction "RH_7") (pintype "bidirectional"))
      (node (ref "R28") (pin "1") (pinfunction "1_1") (pintype "passive"))
    )
    (net (code "138") (name "Net-(R1-Pad1)") (class "Default")
      (node (ref "R1") (pin "1") (pinfunction "1_1") (pintype "passive"))
      (node (ref "T6") (pin "B") (pinfunction "B_B") (pintype "passive"))
    )
    (net (code "139") (name "Net-(R7-Pad2)") (class "Default")
      (node (ref "R7") (pin "2") (pinfunction "2_2") (pintype "passive"))
      (node (ref "X7") (pin "3") (pinfunction "3_3") (pintype "passive"))
    )
    (net (code "140") (name "Net-(R11-Pad1)") (class "Default")
      (node (ref "R11") (pin "1") (pinfunction "1_1") (pintype "passive"))
      (node (ref "T5") (pin "B") (pinfunction "B_B") (pintype "passive"))
    )
    (net (code "141") (name "Net-(RF-POWER-S)") (class "Default")
      (node (ref "RF-POWER") (pin "2") (pinfunction "S_2") (pintype "passive"))
      (node (ref "X7") (pin "5") (pinfunction "5_5") (pintype "passive"))
    )
    (net (code "142") (name "Net-(SQUELCH-A)") (class "Default")
      (node (ref "R2") (pin "1") (pinfunction "1_1") (pintype "passive"))
      (node (ref "SQUELCH") (pin "3") (pinfunction "A_3") (pintype "passive"))
    )
    (net (code "143") (name "Net-(SQUELCH-S)") (class "Default")
      (node (ref "SQUELCH") (pin "2") (pinfunction "S_2") (pintype "passive"))
      (node (ref "X7") (pin "7") (pinfunction "7_7") (pintype "passive"))
    )
    (net (code "144") (name "Net-(SWR/CAL-S)") (class "Default")
      (node (ref "R7") (pin "1") (pinfunction "1_1") (pintype "passive"))
      (node (ref "SWR/CAL") (pin "2") (pinfunction "S_2") (pintype "passive"))
    )
    (net (code "145") (name "Net-(T1-B)") (class "Default")
      (node (ref "R12") (pin "2") (pinfunction "2_2") (pintype "passive"))
      (node (ref "T1") (pin "1") (pinfunction "B_1") (pintype "passive"))
    )
    (net (code "146") (name "Net-(T1-C)") (class "Default")
      (node (ref "T1") (pin "4") (pinfunction "C_4") (pintype "passive"))
      (node (ref "X6") (pin "3") (pinfunction "3_3") (pintype "passive"))
    )
    (net (code "147") (name "Net-(T4-B)") (class "Default")
      (node (ref "R15") (pin "1") (pinfunction "1_1") (pintype "passive"))
      (node (ref "T4") (pin "1") (pinfunction "B_1") (pintype "passive"))
    )
    (net (code "148") (name "Net-(T4-C)") (class "Default")
      (node (ref "R32") (pin "2") (pinfunction "2_2") (pintype "passive"))
      (node (ref "T4") (pin "4") (pinfunction "C_4") (pintype "passive"))
    )
    (net (code "149") (name "Net-(VOLUME-A)") (class "Default")
      (node (ref "VOLUME") (pin "3") (pinfunction "A_3") (pintype "passive"))
      (node (ref "X7") (pin "8") (pinfunction "8_8") (pintype "passive"))
    )
    (net (code "150") (name "Net-(VOLUME-E)") (class "Default")
      (node (ref "VOLUME") (pin "1") (pinfunction "E_1") (pintype "passive"))
      (node (ref "X7") (pin "9") (pinfunction "9_9") (pintype "passive"))
    )
    (net (code "151") (name "Net-(VOLUME-S)") (class "Default")
      (node (ref "VOLUME") (pin "2") (pinfunction "S_2") (pintype "passive"))
      (node (ref "X7") (pin "10") (pinfunction "10_10") (pintype "passive"))
    )
    (net (code "152") (name "Net-(X5B-S)") (class "Default")
      (node (ref "C18") (pin "1") (pinfunction "1_1") (pintype "passive"))
      (node (ref "R8") (pin "2") (pinfunction "2_2") (pintype "passive"))
      (node (ref "X5") (pin "2") (pinfunction "S_2") (pintype "passive"))
    )
    (net (code "153") (name "VCC") (class "Default")
      (node (ref "C13") (pin "2") (pinfunction "2_2") (pintype "passive"))
      (node (ref "C14") (pin "2") (pinfunction "2_2") (pintype "passive"))
      (node (ref "C17") (pin "2") (pinfunction "2_2") (pintype "passive"))
      (node (ref "C23") (pin "2") (pinfunction "2_2") (pintype "passive"))
      (node (ref "C24") (pin "2") (pinfunction "2_2") (pintype "passive"))
      (node (ref "C35") (pin "2") (pinfunction "2_2") (pintype "passive"))
      (node (ref "C4") (pin "+") (pinfunction "+_+") (pintype "passive"))
      (node (ref "D2") (pin "C") (pinfunction "C_C") (pintype "passive"))
      (node (ref "IC3") (pin "28") (pinfunction "VCC_28") (pintype "bidirectional"))
      (node (ref "IC4") (pin "2") (pinfunction "A0_2") (pintype "bidirectional"))
      (node (ref "IC4") (pin "28") (pinfunction "VCC_28") (pintype "bidirectional"))
      (node (ref "IC5") (pin "21") (pinfunction "A0_21") (pintype "input"))
      (node (ref "IC5") (pin "24") (pinfunction "VDD_24") (pintype "power_in"))
      (node (ref "IC6") (pin "24") (pinfunction "VDD_24") (pintype "power_in"))
      (node (ref "IC8") (pin "14") (pinfunction "VDD_14") (pintype "power_in"))
      (node (ref "IC9") (pin "1") (pinfunction "WP_1") (pintype "bidirectional"))
      (node (ref "IC9") (pin "8") (pinfunction "VCC_8") (pintype "power_in"))
      (node (ref "R13") (pin "1") (pinfunction "1_1") (pintype "passive"))
      (node (ref "R21") (pin "1") (pinfunction "1_1") (pintype "passive"))
      (node (ref "R22") (pin "1") (pinfunction "1_1") (pintype "passive"))
      (node (ref "R26") (pin "2") (pinfunction "2_2") (pintype "passive"))
      (node (ref "R27") (pin "2") (pinfunction "2_2") (pintype "passive"))
      (node (ref "R33") (pin "1") (pinfunction "1_1") (pintype "passive"))
      (node (ref "R9") (pin "1") (pinfunction "1_1") (pintype "passive"))
      (node (ref "X1") (pin "1") (pinfunction "1_1") (pintype "passive"))
    )
    (net (code "154") (name "VCCMEM") (class "Default")
      (node (ref "C16") (pin "2") (pinfunction "2_2") (pintype "passive"))
      (node (ref "C8") (pin "2") (pinfunction "2_2") (pintype "passive"))
      (node (ref "D1") (pin "C") (pinfunction "C_C") (pintype "passive"))
      (node (ref "IC1") (pin "21") (pinfunction "VCC_21") (pintype "power_in"))
      (node (ref "IC1") (pin "52") (pinfunction "VCC_52") (pintype "power_in"))
      (node (ref "IC7") (pin "3") (pinfunction "~{WP}_3") (pintype "input"))
      (node (ref "IC7") (pin "7") (pinfunction "~{HOLD}_7") (pintype "input"))
      (node (ref "IC7") (pin "8") (pinfunction "VCC_8") (pintype "power_in"))
      (node (ref "L1") (pin "2") (pinfunction "2_2") (pintype "passive"))
      (node (ref "X2") (pin "1") (pinfunction "S_1") (pintype "passive"))
    )
    (net (code "155") (name "unconnected-(IC1-(A8)PC0-Pad35)") (class "Default")
      (node (ref "IC1") (pin "35") (pinfunction "(A8)PC0_35") (pintype "output"))
    )
    (net (code "156") (name "unconnected-(IC1-(A9)PC1-Pad36)") (class "Default")
      (node (ref "IC1") (pin "36") (pinfunction "(A9)PC1_36") (pintype "output"))
    )
    (net (code "157") (name "unconnected-(IC1-(A10)PC2-Pad37)") (class "Default")
      (node (ref "IC1") (pin "37") (pinfunction "(A10)PC2_37") (pintype "output"))
    )
    (net (code "158") (name "unconnected-(IC1-(A13)PC5-Pad40)") (class "Default")
      (node (ref "IC1") (pin "40") (pinfunction "(A13)PC5_40") (pintype "output"))
    )
    (net (code "159") (name "unconnected-(IC1-(A14)PC6-Pad41)") (class "Default")
      (node (ref "IC1") (pin "41") (pinfunction "(A14)PC6_41") (pintype "output"))
    )
    (net (code "160") (name "unconnected-(IC1-(A15)PC7-Pad42)") (class "Default")
      (node (ref "IC1") (pin "42") (pinfunction "(A15)PC7_42") (pintype "output"))
    )
    (net (code "161") (name "unconnected-(IC1-(AD0)PA0-Pad51)") (class "Default")
      (node (ref "IC1") (pin "51") (pinfunction "(AD0)PA0_51") (pintype "bidirectional"))
    )
    (net (code "162") (name "unconnected-(IC1-(AD1)PA1-Pad50)") (class "Default")
      (node (ref "IC1") (pin "50") (pinfunction "(AD1)PA1_50") (pintype "bidirectional"))
    )
    (net (code "163") (name "unconnected-(IC1-(IC1)PD4-Pad29)") (class "Default")
      (node (ref "IC1") (pin "29") (pinfunction "(IC1)PD4_29") (pintype "bidirectional"))
    )
    (net (code "164") (name "unconnected-(IC1-(OC0)PB4-Pad14)") (class "Default")
      (node (ref "IC1") (pin "14") (pinfunction "(OC0)PB4_14") (pintype "bidirectional"))
    )
    (net (code "165") (name "unconnected-(IC1-(OC1B)PB6-Pad16)") (class "Default")
      (node (ref "IC1") (pin "16") (pinfunction "(OC1B)PB6_16") (pintype "bidirectional"))
    )
    (net (code "166") (name "unconnected-(IC1-(OC2{slash}OC1C)PB7-Pad17)") (class "Default")
      (node (ref "IC1") (pin "17") (pinfunction "(OC2/OC1C)PB7_17") (pintype "bidirectional"))
    )
    (net (code "167") (name "unconnected-(IC1-(OC3A{slash}AIN1)PE3-Pad5)") (class "Default")
      (node (ref "IC1") (pin "5") (pinfunction "(OC3A/AIN1)PE3_5") (pintype "bidirectional"))
    )
    (net (code "168") (name "unconnected-(IC1-(T1)PD6-Pad31)") (class "Default")
      (node (ref "IC1") (pin "31") (pinfunction "(T1)PD6_31") (pintype "bidirectional"))
    )
    (net (code "169") (name "unconnected-(IC1-(T2)PD7-Pad32)") (class "Default")
      (node (ref "IC1") (pin "32") (pinfunction "(T2)PD7_32") (pintype "bidirectional"))
    )
    (net (code "170") (name "unconnected-(IC1-(XCK1)PD5-Pad30)") (class "Default")
      (node (ref "IC1") (pin "30") (pinfunction "(XCK1)PD5_30") (pintype "bidirectional"))
    )
    (net (code "171") (name "unconnected-(IC1-AREF-Pad62)") (class "Default")
      (node (ref "IC1") (pin "62") (pinfunction "AREF_62") (pintype "passive"))
    )
    (net (code "172") (name "unconnected-(IC1-PEN-Pad1)") (class "Default")
      (node (ref "IC1") (pin "1") (pinfunction "PEN_1") (pintype "input"))
    )
    (net (code "173") (name "unconnected-(IC1-PF2(ADC2)-Pad59)") (class "Default")
      (node (ref "IC1") (pin "59") (pinfunction "PF2(ADC2)_59") (pintype "input"))
    )
    (net (code "174") (name "unconnected-(IC1-PF3(ADC3)-Pad58)") (class "Default")
      (node (ref "IC1") (pin "58") (pinfunction "PF3(ADC3)_58") (pintype "input"))
    )
    (net (code "175") (name "unconnected-(IC1-PF4(ADC4{slash}TCK)-Pad57)") (class "Default")
      (node (ref "IC1") (pin "57") (pinfunction "PF4(ADC4/TCK)_57") (pintype "input"))
    )
    (net (code "176") (name "unconnected-(IC1-PF5(ADC5{slash}TMS)-Pad56)") (class "Default")
      (node (ref "IC1") (pin "56") (pinfunction "PF5(ADC5/TMS)_56") (pintype "input"))
    )
    (net (code "177") (name "unconnected-(IC1-PF6(ADC6{slash}TDO)-Pad55)") (class "Default")
      (node (ref "IC1") (pin "55") (pinfunction "PF6(ADC6/TDO)_55") (pintype "input"))
    )
    (net (code "178") (name "unconnected-(IC1-PF7(ADC7{slash}TDI)-Pad54)") (class "Default")
      (node (ref "IC1") (pin "54") (pinfunction "PF7(ADC7/TDI)_54") (pintype "input"))
    )
    (net (code "179") (name "unconnected-(IC1-PG0(WR)-Pad33)") (class "Default")
      (node (ref "IC1") (pin "33") (pinfunction "PG0(WR)_33") (pintype "bidirectional"))
    )
    (net (code "180") (name "unconnected-(IC1-PG1(RD)-Pad34)") (class "Default")
      (node (ref "IC1") (pin "34") (pinfunction "PG1(RD)_34") (pintype "bidirectional"))
    )
    (net (code "181") (name "unconnected-(IC1-PG2(ALE)-Pad43)") (class "Default")
      (node (ref "IC1") (pin "43") (pinfunction "PG2(ALE)_43") (pintype "bidirectional"))
    )
    (net (code "182") (name "unconnected-(IC1-PG3(TOSC2)-Pad18)") (class "Default")
      (node (ref "IC1") (pin "18") (pinfunction "PG3(TOSC2)_18") (pintype "bidirectional"))
    )
    (net (code "183") (name "unconnected-(IC1-PG4(TOSC1)-Pad19)") (class "Default")
      (node (ref "IC1") (pin "19") (pinfunction "PG4(TOSC1)_19") (pintype "bidirectional"))
    )
    (net (code "184") (name "unconnected-(IC3-{slash}OUT12-Pad20)") (class "Default")
      (node (ref "IC3") (pin "20") (pinfunction "/OUT12_20") (pintype "bidirectional"))
    )
    (net (code "185") (name "unconnected-(IC3-{slash}OUT13-Pad21)") (class "Default")
      (node (ref "IC3") (pin "21") (pinfunction "/OUT13_21") (pintype "bidirectional"))
    )
    (net (code "186") (name "unconnected-(IC3-{slash}OUT14-Pad22)") (class "Default")
      (node (ref "IC3") (pin "22") (pinfunction "/OUT14_22") (pintype "bidirectional"))
    )
    (net (code "187") (name "unconnected-(IC3-{slash}OUT15-Pad23)") (class "Default")
      (node (ref "IC3") (pin "23") (pinfunction "/OUT15_23") (pintype "bidirectional"))
    )
    (net (code "188") (name "unconnected-(IC4-{slash}OUT12-Pad20)") (class "Default")
      (node (ref "IC4") (pin "20") (pinfunction "/OUT12_20") (pintype "bidirectional"))
    )
    (net (code "189") (name "unconnected-(IC4-{slash}OUT13-Pad21)") (class "Default")
      (node (ref "IC4") (pin "21") (pinfunction "/OUT13_21") (pintype "bidirectional"))
    )
    (net (code "190") (name "unconnected-(IC4-{slash}OUT14-Pad22)") (class "Default")
      (node (ref "IC4") (pin "22") (pinfunction "/OUT14_22") (pintype "bidirectional"))
    )
    (net (code "191") (name "unconnected-(IC4-{slash}OUT15-Pad23)") (class "Default")
      (node (ref "IC4") (pin "23") (pinfunction "/OUT15_23") (pintype "bidirectional"))
    )
    (net (code "192") (name "unconnected-(IC5-I{slash}O0.3-Pad7)") (class "Default")
      (node (ref "IC5") (pin "7") (pinfunction "I/O0.3_7") (pintype "bidirectional"))
    )
    (net (code "193") (name "unconnected-(IC5-I{slash}O0.4-Pad8)") (class "Default")
      (node (ref "IC5") (pin "8") (pinfunction "I/O0.4_8") (pintype "bidirectional"))
    )
    (net (code "194") (name "unconnected-(IC5-I{slash}O0.5-Pad9)") (class "Default")
      (node (ref "IC5") (pin "9") (pinfunction "I/O0.5_9") (pintype "bidirectional"))
    )
    (net (code "195") (name "unconnected-(IC6-I{slash}O0.7-Pad11)") (class "Default")
      (node (ref "IC6") (pin "11") (pinfunction "I/O0.7_11") (pintype "bidirectional"))
    )
    (net (code "196") (name "unconnected-(IC6-I{slash}O1.5-Pad18)") (class "Default")
      (node (ref "IC6") (pin "18") (pinfunction "I/O1.5_18") (pintype "bidirectional"))
    )
    (net (code "197") (name "unconnected-(IC6-I{slash}O1.6-Pad19)") (class "Default")
      (node (ref "IC6") (pin "19") (pinfunction "I/O1.6_19") (pintype "bidirectional"))
    )
    (net (code "198") (name "unconnected-(IC6-I{slash}O1.7-Pad20)") (class "Default")
      (node (ref "IC6") (pin "20") (pinfunction "I/O1.7_20") (pintype "bidirectional"))
    )
    (net (code "199") (name "unconnected-(IC8-BP3-Pad28)") (class "Default")
      (node (ref "IC8") (pin "28") (pinfunction "BP3_28") (pintype "output"))
    )
    (net (code "200") (name "unconnected-(IC8-CLK-Pad13)") (class "Default")
      (node (ref "IC8") (pin "13") (pinfunction "CLK_13") (pintype "bidirectional"))
    )
    (net (code "201") (name "unconnected-(IC8-S33-Pad64)") (class "Default")
      (node (ref "IC8") (pin "64") (pinfunction "S33_64") (pintype "output"))
    )
    (net (code "202") (name "unconnected-(IC8-S34-Pad2)") (class "Default")
      (node (ref "IC8") (pin "2") (pinfunction "S34_2") (pintype "output"))
    )
    (net (code "203") (name "unconnected-(IC8-S35-Pad3)") (class "Default")
      (node (ref "IC8") (pin "3") (pinfunction "S35_3") (pintype "output"))
    )
    (net (code "204") (name "unconnected-(IC8-S36-Pad4)") (class "Default")
      (node (ref "IC8") (pin "4") (pinfunction "S36_4") (pintype "output"))
    )
    (net (code "205") (name "unconnected-(IC8-S37-Pad5)") (class "Default")
      (node (ref "IC8") (pin "5") (pinfunction "S37_5") (pintype "output"))
    )
    (net (code "206") (name "unconnected-(IC8-S38-Pad6)") (class "Default")
      (node (ref "IC8") (pin "6") (pinfunction "S38_6") (pintype "output"))
    )
    (net (code "207") (name "unconnected-(IC8-S39-Pad7)") (class "Default")
      (node (ref "IC8") (pin "7") (pinfunction "S39_7") (pintype "output"))
    )
    (net (code "208") (name "unconnected-(IC8-SYNC-Pad12)") (class "Default")
      (node (ref "IC8") (pin "12") (pinfunction "SYNC_12") (pintype "bidirectional"))
    )
    (net (code "209") (name "unconnected-(RF-POWER-A-Pad3)") (class "Default")
      (node (ref "RF-POWER") (pin "3") (pinfunction "A_3") (pintype "passive"))
    )
  )
)
